# KEY_SCHEMATIC.net
KiCad netlist of a schematic drawn in EasyEDA
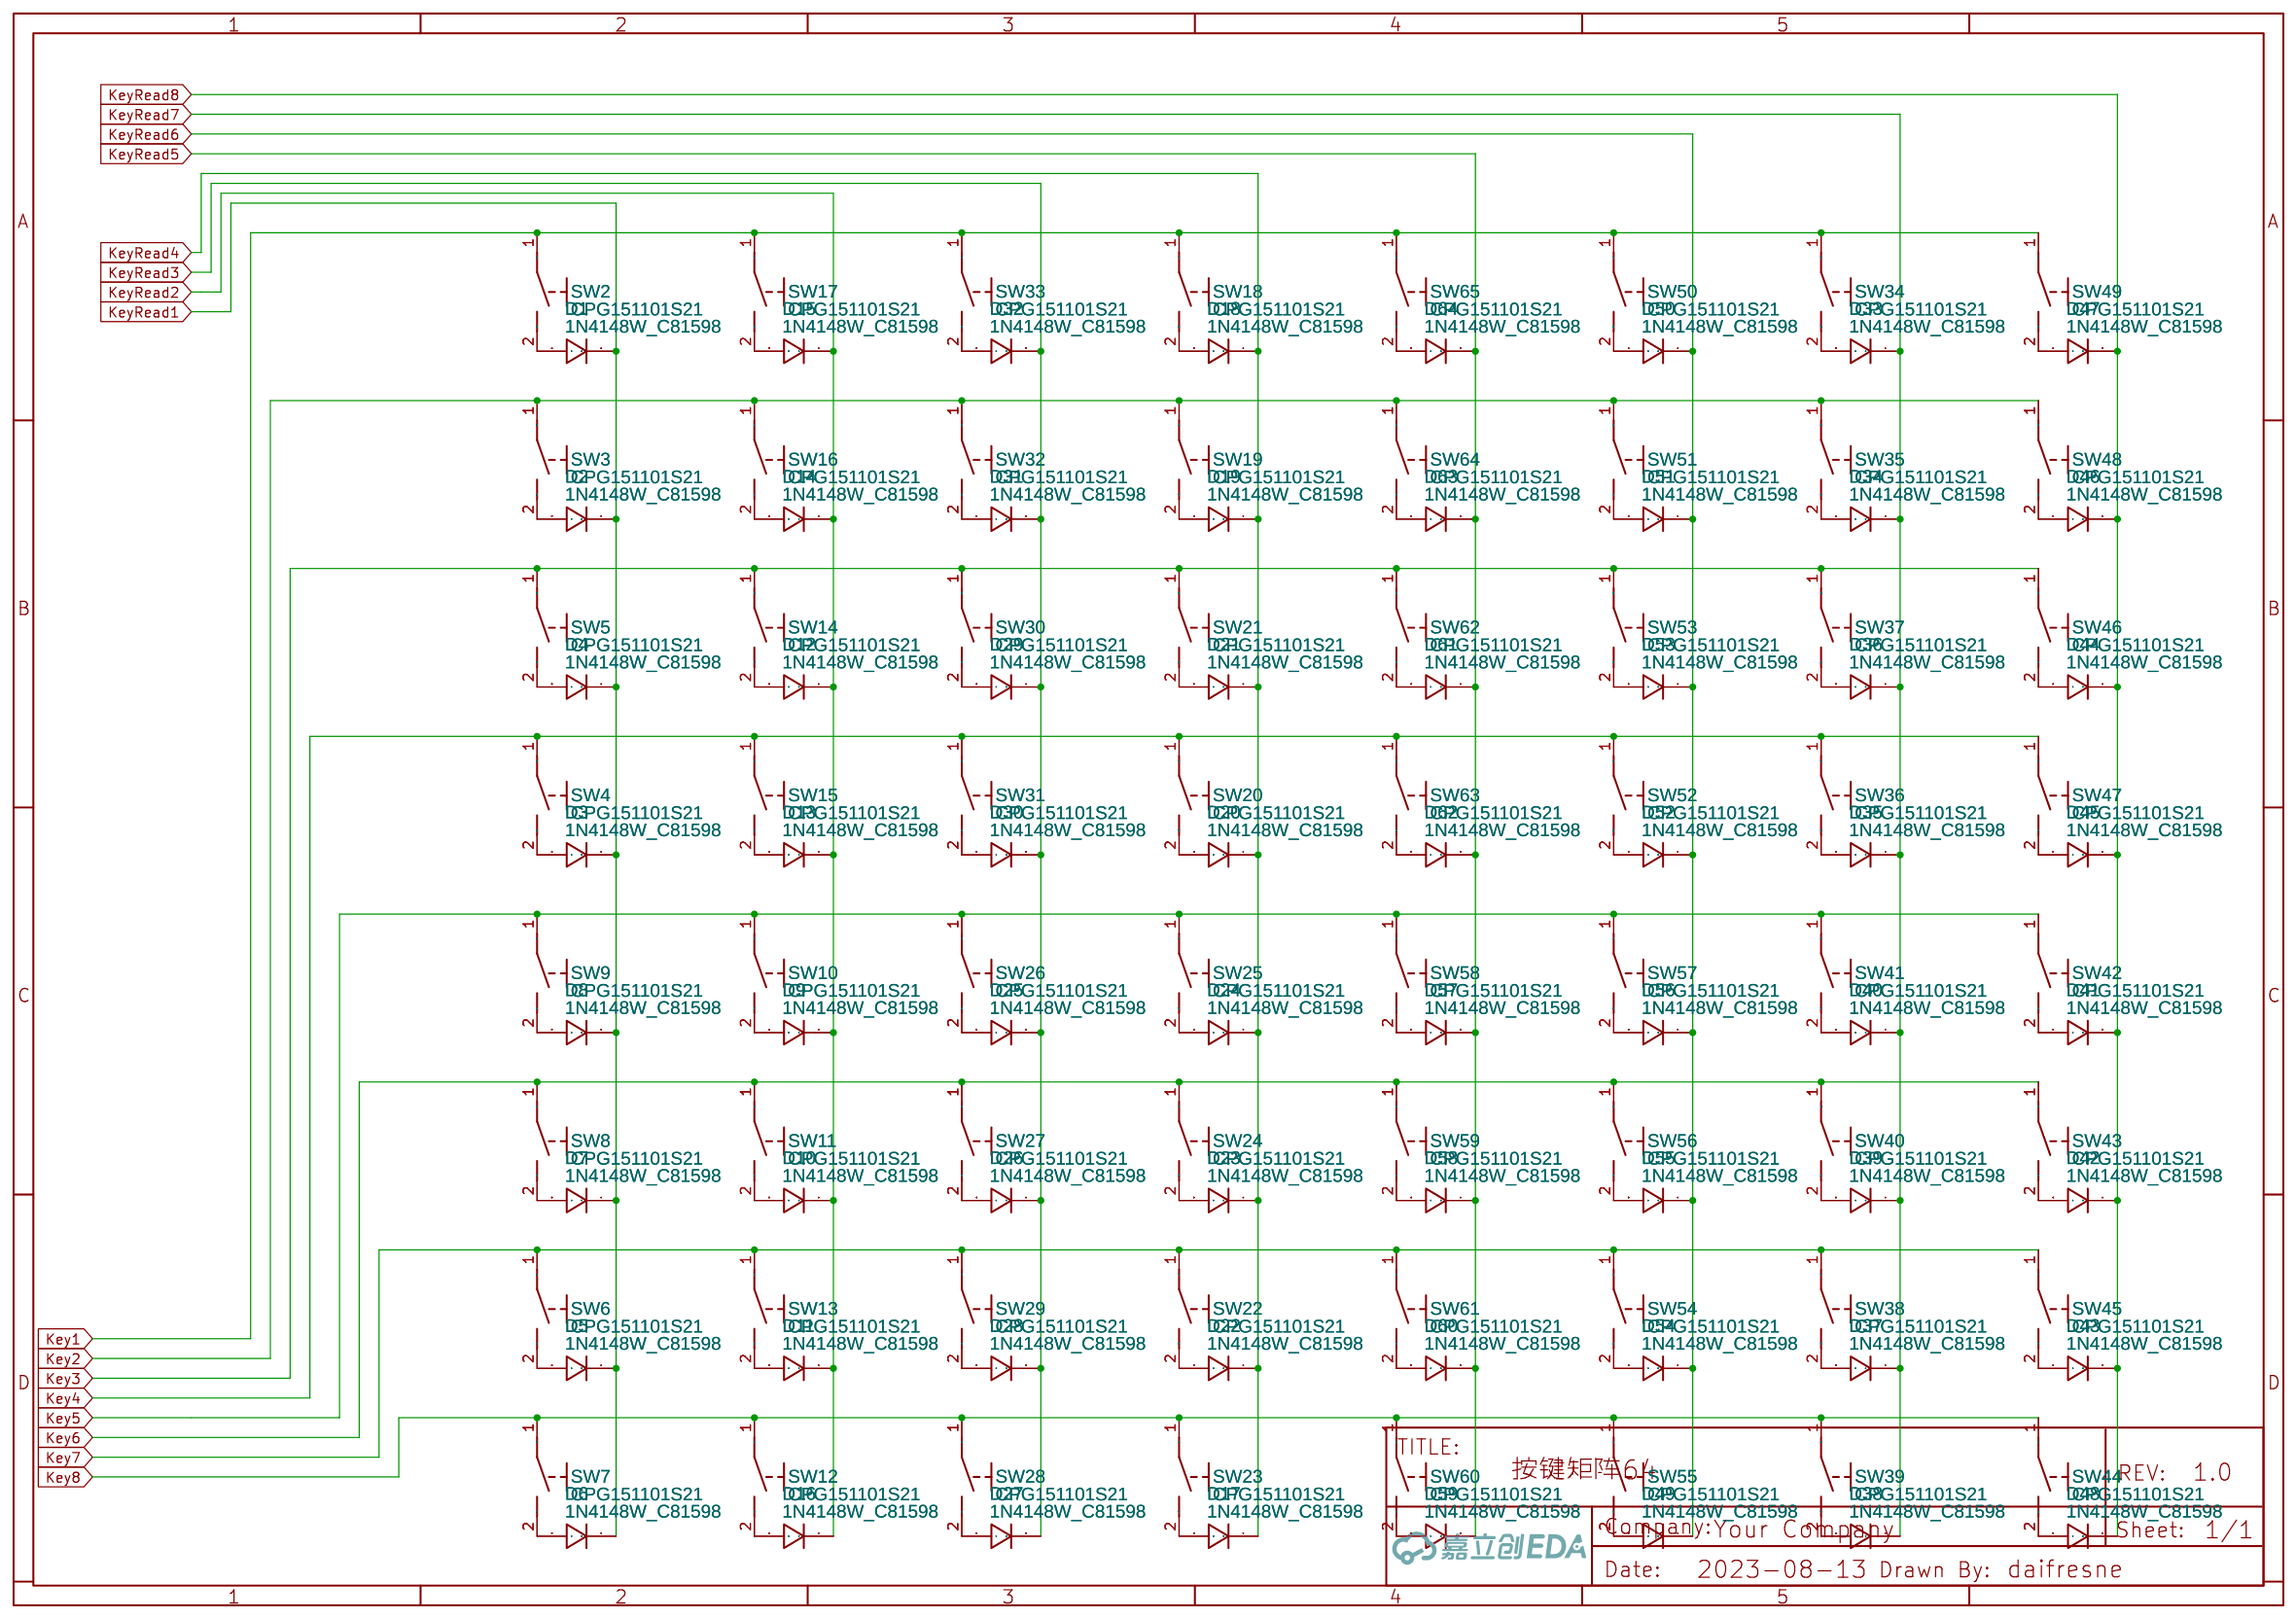
[diagram p0: 按键矩阵64]
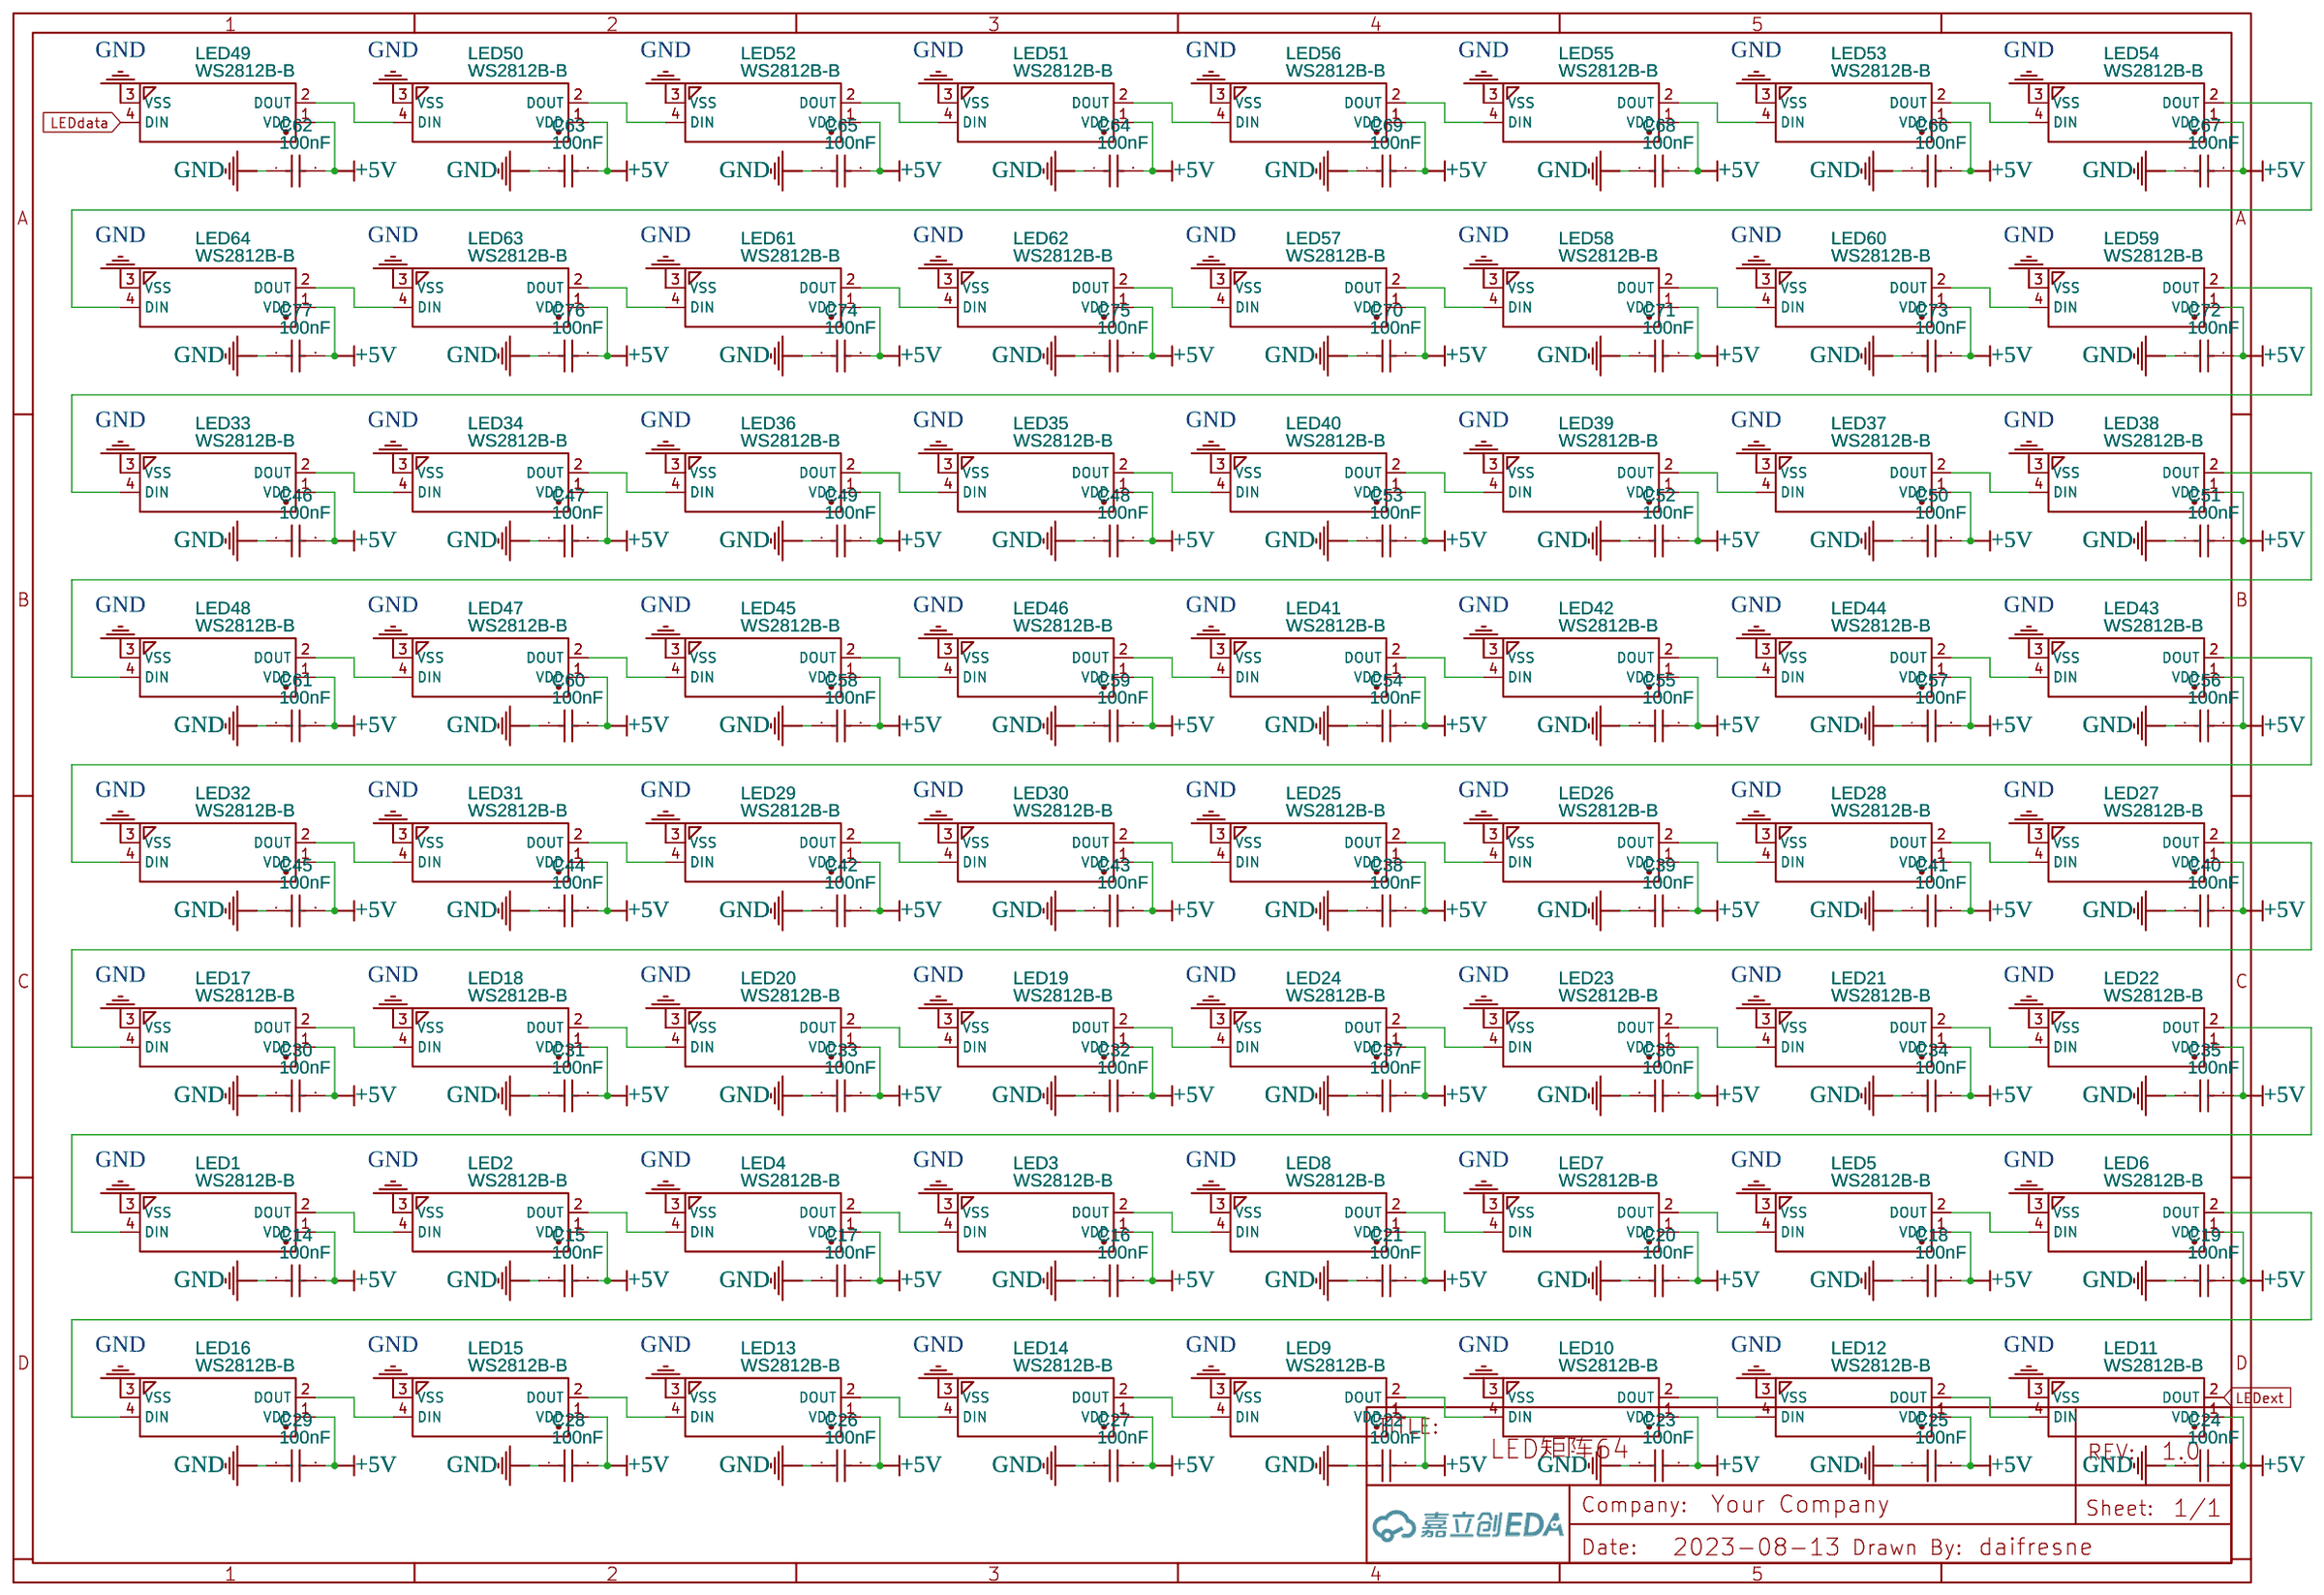
[diagram p1: LED矩阵64]

(export (version "E")
  (design (tool "Eeschema 10.0.6"))
  (components
    (comp (ref "D1")
      (value "1N4148W_C81598")
      (fields (field (name "Manufacturer") "ST(先科)"))
      (libsource (lib "") (part "1N4148W_C81598"))
    )
    (comp (ref "D2")
      (value "1N4148W_C81598")
      (fields (field (name "Manufacturer") "ST(先科)"))
      (libsource (lib "") (part "1N4148W_C81598"))
    )
    (comp (ref "D3")
      (value "1N4148W_C81598")
      (fields (field (name "Manufacturer") "ST(先科)"))
      (libsource (lib "") (part "1N4148W_C81598"))
    )
    (comp (ref "D4")
      (value "1N4148W_C81598")
      (fields (field (name "Manufacturer") "ST(先科)"))
      (libsource (lib "") (part "1N4148W_C81598"))
    )
    (comp (ref "D5")
      (value "1N4148W_C81598")
      (fields (field (name "Manufacturer") "ST(先科)"))
      (libsource (lib "") (part "1N4148W_C81598"))
    )
    (comp (ref "D6")
      (value "1N4148W_C81598")
      (fields (field (name "Manufacturer") "ST(先科)"))
      (libsource (lib "") (part "1N4148W_C81598"))
    )
    (comp (ref "D7")
      (value "1N4148W_C81598")
      (fields (field (name "Manufacturer") "ST(先科)"))
      (libsource (lib "") (part "1N4148W_C81598"))
    )
    (comp (ref "D8")
      (value "1N4148W_C81598")
      (fields (field (name "Manufacturer") "ST(先科)"))
      (libsource (lib "") (part "1N4148W_C81598"))
    )
    (comp (ref "D9")
      (value "1N4148W_C81598")
      (fields (field (name "Manufacturer") "ST(先科)"))
      (libsource (lib "") (part "1N4148W_C81598"))
    )
    (comp (ref "D10")
      (value "1N4148W_C81598")
      (fields (field (name "Manufacturer") "ST(先科)"))
      (libsource (lib "") (part "1N4148W_C81598"))
    )
    (comp (ref "D11")
      (value "1N4148W_C81598")
      (fields (field (name "Manufacturer") "ST(先科)"))
      (libsource (lib "") (part "1N4148W_C81598"))
    )
    (comp (ref "D12")
      (value "1N4148W_C81598")
      (fields (field (name "Manufacturer") "ST(先科)"))
      (libsource (lib "") (part "1N4148W_C81598"))
    )
    (comp (ref "D13")
      (value "1N4148W_C81598")
      (fields (field (name "Manufacturer") "ST(先科)"))
      (libsource (lib "") (part "1N4148W_C81598"))
    )
    (comp (ref "D14")
      (value "1N4148W_C81598")
      (fields (field (name "Manufacturer") "ST(先科)"))
      (libsource (lib "") (part "1N4148W_C81598"))
    )
    (comp (ref "D15")
      (value "1N4148W_C81598")
      (fields (field (name "Manufacturer") "ST(先科)"))
      (libsource (lib "") (part "1N4148W_C81598"))
    )
    (comp (ref "D16")
      (value "1N4148W_C81598")
      (fields (field (name "Manufacturer") "ST(先科)"))
      (libsource (lib "") (part "1N4148W_C81598"))
    )
    (comp (ref "D17")
      (value "1N4148W_C81598")
      (fields (field (name "Manufacturer") "ST(先科)"))
      (libsource (lib "") (part "1N4148W_C81598"))
    )
    (comp (ref "D18")
      (value "1N4148W_C81598")
      (fields (field (name "Manufacturer") "ST(先科)"))
      (libsource (lib "") (part "1N4148W_C81598"))
    )
    (comp (ref "D19")
      (value "1N4148W_C81598")
      (fields (field (name "Manufacturer") "ST(先科)"))
      (libsource (lib "") (part "1N4148W_C81598"))
    )
    (comp (ref "D20")
      (value "1N4148W_C81598")
      (fields (field (name "Manufacturer") "ST(先科)"))
      (libsource (lib "") (part "1N4148W_C81598"))
    )
    (comp (ref "D21")
      (value "1N4148W_C81598")
      (fields (field (name "Manufacturer") "ST(先科)"))
      (libsource (lib "") (part "1N4148W_C81598"))
    )
    (comp (ref "D22")
      (value "1N4148W_C81598")
      (fields (field (name "Manufacturer") "ST(先科)"))
      (libsource (lib "") (part "1N4148W_C81598"))
    )
    (comp (ref "D23")
      (value "1N4148W_C81598")
      (fields (field (name "Manufacturer") "ST(先科)"))
      (libsource (lib "") (part "1N4148W_C81598"))
    )
    (comp (ref "D24")
      (value "1N4148W_C81598")
      (fields (field (name "Manufacturer") "ST(先科)"))
      (libsource (lib "") (part "1N4148W_C81598"))
    )
    (comp (ref "D25")
      (value "1N4148W_C81598")
      (fields (field (name "Manufacturer") "ST(先科)"))
      (libsource (lib "") (part "1N4148W_C81598"))
    )
    (comp (ref "D26")
      (value "1N4148W_C81598")
      (fields (field (name "Manufacturer") "ST(先科)"))
      (libsource (lib "") (part "1N4148W_C81598"))
    )
    (comp (ref "D27")
      (value "1N4148W_C81598")
      (fields (field (name "Manufacturer") "ST(先科)"))
      (libsource (lib "") (part "1N4148W_C81598"))
    )
    (comp (ref "D28")
      (value "1N4148W_C81598")
      (fields (field (name "Manufacturer") "ST(先科)"))
      (libsource (lib "") (part "1N4148W_C81598"))
    )
    (comp (ref "D29")
      (value "1N4148W_C81598")
      (fields (field (name "Manufacturer") "ST(先科)"))
      (libsource (lib "") (part "1N4148W_C81598"))
    )
    (comp (ref "D30")
      (value "1N4148W_C81598")
      (fields (field (name "Manufacturer") "ST(先科)"))
      (libsource (lib "") (part "1N4148W_C81598"))
    )
    (comp (ref "D31")
      (value "1N4148W_C81598")
      (fields (field (name "Manufacturer") "ST(先科)"))
      (libsource (lib "") (part "1N4148W_C81598"))
    )
    (comp (ref "D32")
      (value "1N4148W_C81598")
      (fields (field (name "Manufacturer") "ST(先科)"))
      (libsource (lib "") (part "1N4148W_C81598"))
    )
    (comp (ref "D33")
      (value "1N4148W_C81598")
      (fields (field (name "Manufacturer") "ST(先科)"))
      (libsource (lib "") (part "1N4148W_C81598"))
    )
    (comp (ref "D34")
      (value "1N4148W_C81598")
      (fields (field (name "Manufacturer") "ST(先科)"))
      (libsource (lib "") (part "1N4148W_C81598"))
    )
    (comp (ref "D35")
      (value "1N4148W_C81598")
      (fields (field (name "Manufacturer") "ST(先科)"))
      (libsource (lib "") (part "1N4148W_C81598"))
    )
    (comp (ref "D36")
      (value "1N4148W_C81598")
      (fields (field (name "Manufacturer") "ST(先科)"))
      (libsource (lib "") (part "1N4148W_C81598"))
    )
    (comp (ref "D37")
      (value "1N4148W_C81598")
      (fields (field (name "Manufacturer") "ST(先科)"))
      (libsource (lib "") (part "1N4148W_C81598"))
    )
    (comp (ref "D38")
      (value "1N4148W_C81598")
      (fields (field (name "Manufacturer") "ST(先科)"))
      (libsource (lib "") (part "1N4148W_C81598"))
    )
    (comp (ref "D39")
      (value "1N4148W_C81598")
      (fields (field (name "Manufacturer") "ST(先科)"))
      (libsource (lib "") (part "1N4148W_C81598"))
    )
    (comp (ref "D40")
      (value "1N4148W_C81598")
      (fields (field (name "Manufacturer") "ST(先科)"))
      (libsource (lib "") (part "1N4148W_C81598"))
    )
    (comp (ref "D41")
      (value "1N4148W_C81598")
      (fields (field (name "Manufacturer") "ST(先科)"))
      (libsource (lib "") (part "1N4148W_C81598"))
    )
    (comp (ref "D42")
      (value "1N4148W_C81598")
      (fields (field (name "Manufacturer") "ST(先科)"))
      (libsource (lib "") (part "1N4148W_C81598"))
    )
    (comp (ref "D43")
      (value "1N4148W_C81598")
      (fields (field (name "Manufacturer") "ST(先科)"))
      (libsource (lib "") (part "1N4148W_C81598"))
    )
    (comp (ref "D44")
      (value "1N4148W_C81598")
      (fields (field (name "Manufacturer") "ST(先科)"))
      (libsource (lib "") (part "1N4148W_C81598"))
    )
    (comp (ref "D45")
      (value "1N4148W_C81598")
      (fields (field (name "Manufacturer") "ST(先科)"))
      (libsource (lib "") (part "1N4148W_C81598"))
    )
    (comp (ref "D46")
      (value "1N4148W_C81598")
      (fields (field (name "Manufacturer") "ST(先科)"))
      (libsource (lib "") (part "1N4148W_C81598"))
    )
    (comp (ref "D47")
      (value "1N4148W_C81598")
      (fields (field (name "Manufacturer") "ST(先科)"))
      (libsource (lib "") (part "1N4148W_C81598"))
    )
    (comp (ref "D48")
      (value "1N4148W_C81598")
      (fields (field (name "Manufacturer") "ST(先科)"))
      (libsource (lib "") (part "1N4148W_C81598"))
    )
    (comp (ref "D49")
      (value "1N4148W_C81598")
      (fields (field (name "Manufacturer") "ST(先科)"))
      (libsource (lib "") (part "1N4148W_C81598"))
    )
    (comp (ref "D50")
      (value "1N4148W_C81598")
      (fields (field (name "Manufacturer") "ST(先科)"))
      (libsource (lib "") (part "1N4148W_C81598"))
    )
    (comp (ref "D51")
      (value "1N4148W_C81598")
      (fields (field (name "Manufacturer") "ST(先科)"))
      (libsource (lib "") (part "1N4148W_C81598"))
    )
    (comp (ref "D52")
      (value "1N4148W_C81598")
      (fields (field (name "Manufacturer") "ST(先科)"))
      (libsource (lib "") (part "1N4148W_C81598"))
    )
    (comp (ref "D53")
      (value "1N4148W_C81598")
      (fields (field (name "Manufacturer") "ST(先科)"))
      (libsource (lib "") (part "1N4148W_C81598"))
    )
    (comp (ref "D54")
      (value "1N4148W_C81598")
      (fields (field (name "Manufacturer") "ST(先科)"))
      (libsource (lib "") (part "1N4148W_C81598"))
    )
    (comp (ref "D55")
      (value "1N4148W_C81598")
      (fields (field (name "Manufacturer") "ST(先科)"))
      (libsource (lib "") (part "1N4148W_C81598"))
    )
    (comp (ref "D56")
      (value "1N4148W_C81598")
      (fields (field (name "Manufacturer") "ST(先科)"))
      (libsource (lib "") (part "1N4148W_C81598"))
    )
    (comp (ref "D57")
      (value "1N4148W_C81598")
      (fields (field (name "Manufacturer") "ST(先科)"))
      (libsource (lib "") (part "1N4148W_C81598"))
    )
    (comp (ref "D58")
      (value "1N4148W_C81598")
      (fields (field (name "Manufacturer") "ST(先科)"))
      (libsource (lib "") (part "1N4148W_C81598"))
    )
    (comp (ref "D59")
      (value "1N4148W_C81598")
      (fields (field (name "Manufacturer") "ST(先科)"))
      (libsource (lib "") (part "1N4148W_C81598"))
    )
    (comp (ref "D60")
      (value "1N4148W_C81598")
      (fields (field (name "Manufacturer") "ST(先科)"))
      (libsource (lib "") (part "1N4148W_C81598"))
    )
    (comp (ref "D61")
      (value "1N4148W_C81598")
      (fields (field (name "Manufacturer") "ST(先科)"))
      (libsource (lib "") (part "1N4148W_C81598"))
    )
    (comp (ref "D62")
      (value "1N4148W_C81598")
      (fields (field (name "Manufacturer") "ST(先科)"))
      (libsource (lib "") (part "1N4148W_C81598"))
    )
    (comp (ref "D63")
      (value "1N4148W_C81598")
      (fields (field (name "Manufacturer") "ST(先科)"))
      (libsource (lib "") (part "1N4148W_C81598"))
    )
    (comp (ref "D64")
      (value "1N4148W_C81598")
      (fields (field (name "Manufacturer") "ST(先科)"))
      (libsource (lib "") (part "1N4148W_C81598"))
    )
    (comp (ref "SW2")
      (value "CPG151101S21")
      (fields (field (name "Manufacturer") "Kailh(凯华)"))
      (libsource (lib "") (part "CPG151101S21"))
    )
    (comp (ref "SW3")
      (value "CPG151101S21")
      (fields (field (name "Manufacturer") "Kailh(凯华)"))
      (libsource (lib "") (part "CPG151101S21"))
    )
    (comp (ref "SW4")
      (value "CPG151101S21")
      (fields (field (name "Manufacturer") "Kailh(凯华)"))
      (libsource (lib "") (part "CPG151101S21"))
    )
    (comp (ref "SW5")
      (value "CPG151101S21")
      (fields (field (name "Manufacturer") "Kailh(凯华)"))
      (libsource (lib "") (part "CPG151101S21"))
    )
    (comp (ref "SW6")
      (value "CPG151101S21")
      (fields (field (name "Manufacturer") "Kailh(凯华)"))
      (libsource (lib "") (part "CPG151101S21"))
    )
    (comp (ref "SW7")
      (value "CPG151101S21")
      (fields (field (name "Manufacturer") "Kailh(凯华)"))
      (libsource (lib "") (part "CPG151101S21"))
    )
    (comp (ref "SW8")
      (value "CPG151101S21")
      (fields (field (name "Manufacturer") "Kailh(凯华)"))
      (libsource (lib "") (part "CPG151101S21"))
    )
    (comp (ref "SW9")
      (value "CPG151101S21")
      (fields (field (name "Manufacturer") "Kailh(凯华)"))
      (libsource (lib "") (part "CPG151101S21"))
    )
    (comp (ref "SW10")
      (value "CPG151101S21")
      (fields (field (name "Manufacturer") "Kailh(凯华)"))
      (libsource (lib "") (part "CPG151101S21"))
    )
    (comp (ref "SW11")
      (value "CPG151101S21")
      (fields (field (name "Manufacturer") "Kailh(凯华)"))
      (libsource (lib "") (part "CPG151101S21"))
    )
    (comp (ref "SW12")
      (value "CPG151101S21")
      (fields (field (name "Manufacturer") "Kailh(凯华)"))
      (libsource (lib "") (part "CPG151101S21"))
    )
    (comp (ref "SW13")
      (value "CPG151101S21")
      (fields (field (name "Manufacturer") "Kailh(凯华)"))
      (libsource (lib "") (part "CPG151101S21"))
    )
    (comp (ref "SW14")
      (value "CPG151101S21")
      (fields (field (name "Manufacturer") "Kailh(凯华)"))
      (libsource (lib "") (part "CPG151101S21"))
    )
    (comp (ref "SW15")
      (value "CPG151101S21")
      (fields (field (name "Manufacturer") "Kailh(凯华)"))
      (libsource (lib "") (part "CPG151101S21"))
    )
    (comp (ref "SW16")
      (value "CPG151101S21")
      (fields (field (name "Manufacturer") "Kailh(凯华)"))
      (libsource (lib "") (part "CPG151101S21"))
    )
    (comp (ref "SW17")
      (value "CPG151101S21")
      (fields (field (name "Manufacturer") "Kailh(凯华)"))
      (libsource (lib "") (part "CPG151101S21"))
    )
    (comp (ref "SW18")
      (value "CPG151101S21")
      (fields (field (name "Manufacturer") "Kailh(凯华)"))
      (libsource (lib "") (part "CPG151101S21"))
    )
    (comp (ref "SW19")
      (value "CPG151101S21")
      (fields (field (name "Manufacturer") "Kailh(凯华)"))
      (libsource (lib "") (part "CPG151101S21"))
    )
    (comp (ref "SW20")
      (value "CPG151101S21")
      (fields (field (name "Manufacturer") "Kailh(凯华)"))
      (libsource (lib "") (part "CPG151101S21"))
    )
    (comp (ref "SW21")
      (value "CPG151101S21")
      (fields (field (name "Manufacturer") "Kailh(凯华)"))
      (libsource (lib "") (part "CPG151101S21"))
    )
    (comp (ref "SW22")
      (value "CPG151101S21")
      (fields (field (name "Manufacturer") "Kailh(凯华)"))
      (libsource (lib "") (part "CPG151101S21"))
    )
    (comp (ref "SW23")
      (value "CPG151101S21")
      (fields (field (name "Manufacturer") "Kailh(凯华)"))
      (libsource (lib "") (part "CPG151101S21"))
    )
    (comp (ref "SW24")
      (value "CPG151101S21")
      (fields (field (name "Manufacturer") "Kailh(凯华)"))
      (libsource (lib "") (part "CPG151101S21"))
    )
    (comp (ref "SW25")
      (value "CPG151101S21")
      (fields (field (name "Manufacturer") "Kailh(凯华)"))
      (libsource (lib "") (part "CPG151101S21"))
    )
    (comp (ref "SW26")
      (value "CPG151101S21")
      (fields (field (name "Manufacturer") "Kailh(凯华)"))
      (libsource (lib "") (part "CPG151101S21"))
    )
    (comp (ref "SW27")
      (value "CPG151101S21")
      (fields (field (name "Manufacturer") "Kailh(凯华)"))
      (libsource (lib "") (part "CPG151101S21"))
    )
    (comp (ref "SW28")
      (value "CPG151101S21")
      (fields (field (name "Manufacturer") "Kailh(凯华)"))
      (libsource (lib "") (part "CPG151101S21"))
    )
    (comp (ref "SW29")
      (value "CPG151101S21")
      (fields (field (name "Manufacturer") "Kailh(凯华)"))
      (libsource (lib "") (part "CPG151101S21"))
    )
    (comp (ref "SW30")
      (value "CPG151101S21")
      (fields (field (name "Manufacturer") "Kailh(凯华)"))
      (libsource (lib "") (part "CPG151101S21"))
    )
    (comp (ref "SW31")
      (value "CPG151101S21")
      (fields (field (name "Manufacturer") "Kailh(凯华)"))
      (libsource (lib "") (part "CPG151101S21"))
    )
    (comp (ref "SW32")
      (value "CPG151101S21")
      (fields (field (name "Manufacturer") "Kailh(凯华)"))
      (libsource (lib "") (part "CPG151101S21"))
    )
    (comp (ref "SW33")
      (value "CPG151101S21")
      (fields (field (name "Manufacturer") "Kailh(凯华)"))
      (libsource (lib "") (part "CPG151101S21"))
    )
    (comp (ref "SW34")
      (value "CPG151101S21")
      (fields (field (name "Manufacturer") "Kailh(凯华)"))
      (libsource (lib "") (part "CPG151101S21"))
    )
    (comp (ref "SW35")
      (value "CPG151101S21")
      (fields (field (name "Manufacturer") "Kailh(凯华)"))
      (libsource (lib "") (part "CPG151101S21"))
    )
    (comp (ref "SW36")
      (value "CPG151101S21")
      (fields (field (name "Manufacturer") "Kailh(凯华)"))
      (libsource (lib "") (part "CPG151101S21"))
    )
    (comp (ref "SW37")
      (value "CPG151101S21")
      (fields (field (name "Manufacturer") "Kailh(凯华)"))
      (libsource (lib "") (part "CPG151101S21"))
    )
    (comp (ref "SW38")
      (value "CPG151101S21")
      (fields (field (name "Manufacturer") "Kailh(凯华)"))
      (libsource (lib "") (part "CPG151101S21"))
    )
    (comp (ref "SW39")
      (value "CPG151101S21")
      (fields (field (name "Manufacturer") "Kailh(凯华)"))
      (libsource (lib "") (part "CPG151101S21"))
    )
    (comp (ref "SW40")
      (value "CPG151101S21")
      (fields (field (name "Manufacturer") "Kailh(凯华)"))
      (libsource (lib "") (part "CPG151101S21"))
    )
    (comp (ref "SW41")
      (value "CPG151101S21")
      (fields (field (name "Manufacturer") "Kailh(凯华)"))
      (libsource (lib "") (part "CPG151101S21"))
    )
    (comp (ref "SW42")
      (value "CPG151101S21")
      (fields (field (name "Manufacturer") "Kailh(凯华)"))
      (libsource (lib "") (part "CPG151101S21"))
    )
    (comp (ref "SW43")
      (value "CPG151101S21")
      (fields (field (name "Manufacturer") "Kailh(凯华)"))
      (libsource (lib "") (part "CPG151101S21"))
    )
    (comp (ref "SW44")
      (value "CPG151101S21")
      (fields (field (name "Manufacturer") "Kailh(凯华)"))
      (libsource (lib "") (part "CPG151101S21"))
    )
    (comp (ref "SW45")
      (value "CPG151101S21")
      (fields (field (name "Manufacturer") "Kailh(凯华)"))
      (libsource (lib "") (part "CPG151101S21"))
    )
    (comp (ref "SW46")
      (value "CPG151101S21")
      (fields (field (name "Manufacturer") "Kailh(凯华)"))
      (libsource (lib "") (part "CPG151101S21"))
    )
    (comp (ref "SW47")
      (value "CPG151101S21")
      (fields (field (name "Manufacturer") "Kailh(凯华)"))
      (libsource (lib "") (part "CPG151101S21"))
    )
    (comp (ref "SW48")
      (value "CPG151101S21")
      (fields (field (name "Manufacturer") "Kailh(凯华)"))
      (libsource (lib "") (part "CPG151101S21"))
    )
    (comp (ref "SW49")
      (value "CPG151101S21")
      (fields (field (name "Manufacturer") "Kailh(凯华)"))
      (libsource (lib "") (part "CPG151101S21"))
    )
    (comp (ref "SW50")
      (value "CPG151101S21")
      (fields (field (name "Manufacturer") "Kailh(凯华)"))
      (libsource (lib "") (part "CPG151101S21"))
    )
    (comp (ref "SW51")
      (value "CPG151101S21")
      (fields (field (name "Manufacturer") "Kailh(凯华)"))
      (libsource (lib "") (part "CPG151101S21"))
    )
    (comp (ref "SW52")
      (value "CPG151101S21")
      (fields (field (name "Manufacturer") "Kailh(凯华)"))
      (libsource (lib "") (part "CPG151101S21"))
    )
    (comp (ref "SW53")
      (value "CPG151101S21")
      (fields (field (name "Manufacturer") "Kailh(凯华)"))
      (libsource (lib "") (part "CPG151101S21"))
    )
    (comp (ref "SW54")
      (value "CPG151101S21")
      (fields (field (name "Manufacturer") "Kailh(凯华)"))
      (libsource (lib "") (part "CPG151101S21"))
    )
    (comp (ref "SW55")
      (value "CPG151101S21")
      (fields (field (name "Manufacturer") "Kailh(凯华)"))
      (libsource (lib "") (part "CPG151101S21"))
    )
    (comp (ref "SW56")
      (value "CPG151101S21")
      (fields (field (name "Manufacturer") "Kailh(凯华)"))
      (libsource (lib "") (part "CPG151101S21"))
    )
    (comp (ref "SW57")
      (value "CPG151101S21")
      (fields (field (name "Manufacturer") "Kailh(凯华)"))
      (libsource (lib "") (part "CPG151101S21"))
    )
    (comp (ref "SW58")
      (value "CPG151101S21")
      (fields (field (name "Manufacturer") "Kailh(凯华)"))
      (libsource (lib "") (part "CPG151101S21"))
    )
    (comp (ref "SW59")
      (value "CPG151101S21")
      (fields (field (name "Manufacturer") "Kailh(凯华)"))
      (libsource (lib "") (part "CPG151101S21"))
    )
    (comp (ref "SW60")
      (value "CPG151101S21")
      (fields (field (name "Manufacturer") "Kailh(凯华)"))
      (libsource (lib "") (part "CPG151101S21"))
    )
    (comp (ref "SW61")
      (value "CPG151101S21")
      (fields (field (name "Manufacturer") "Kailh(凯华)"))
      (libsource (lib "") (part "CPG151101S21"))
    )
    (comp (ref "SW62")
      (value "CPG151101S21")
      (fields (field (name "Manufacturer") "Kailh(凯华)"))
      (libsource (lib "") (part "CPG151101S21"))
    )
    (comp (ref "SW63")
      (value "CPG151101S21")
      (fields (field (name "Manufacturer") "Kailh(凯华)"))
      (libsource (lib "") (part "CPG151101S21"))
    )
    (comp (ref "SW64")
      (value "CPG151101S21")
      (fields (field (name "Manufacturer") "Kailh(凯华)"))
      (libsource (lib "") (part "CPG151101S21"))
    )
    (comp (ref "SW65")
      (value "CPG151101S21")
      (fields (field (name "Manufacturer") "Kailh(凯华)"))
      (libsource (lib "") (part "CPG151101S21"))
    )
    (comp (ref "C14")
      (value "100nF")
      (fields
        (field (name "Manufacturer Part") "CC0603KRX7R8BB104")
        (field (name "Manufacturer") "YAGEO(国巨)")
      )
      (libsource (lib "") (part "CC0603KRX7R8BB104"))
    )
    (comp (ref "C15")
      (value "100nF")
      (fields
        (field (name "Manufacturer Part") "CC0603KRX7R8BB104")
        (field (name "Manufacturer") "YAGEO(国巨)")
      )
      (libsource (lib "") (part "CC0603KRX7R8BB104"))
    )
    (comp (ref "C16")
      (value "100nF")
      (fields
        (field (name "Manufacturer Part") "CC0603KRX7R8BB104")
        (field (name "Manufacturer") "YAGEO(国巨)")
      )
      (libsource (lib "") (part "CC0603KRX7R8BB104"))
    )
    (comp (ref "C17")
      (value "100nF")
      (fields
        (field (name "Manufacturer Part") "CC0603KRX7R8BB104")
        (field (name "Manufacturer") "YAGEO(国巨)")
      )
      (libsource (lib "") (part "CC0603KRX7R8BB104"))
    )
    (comp (ref "C18")
      (value "100nF")
      (fields
        (field (name "Manufacturer Part") "CC0603KRX7R8BB104")
        (field (name "Manufacturer") "YAGEO(国巨)")
      )
      (libsource (lib "") (part "CC0603KRX7R8BB104"))
    )
    (comp (ref "C19")
      (value "100nF")
      (fields
        (field (name "Manufacturer Part") "CC0603KRX7R8BB104")
        (field (name "Manufacturer") "YAGEO(国巨)")
      )
      (libsource (lib "") (part "CC0603KRX7R8BB104"))
    )
    (comp (ref "C20")
      (value "100nF")
      (fields
        (field (name "Manufacturer Part") "CC0603KRX7R8BB104")
        (field (name "Manufacturer") "YAGEO(国巨)")
      )
      (libsource (lib "") (part "CC0603KRX7R8BB104"))
    )
    (comp (ref "C21")
      (value "100nF")
      (fields
        (field (name "Manufacturer Part") "CC0603KRX7R8BB104")
        (field (name "Manufacturer") "YAGEO(国巨)")
      )
      (libsource (lib "") (part "CC0603KRX7R8BB104"))
    )
    (comp (ref "C22")
      (value "100nF")
      (fields
        (field (name "Manufacturer Part") "CC0603KRX7R8BB104")
        (field (name "Manufacturer") "YAGEO(国巨)")
      )
      (libsource (lib "") (part "CC0603KRX7R8BB104"))
    )
    (comp (ref "C23")
      (value "100nF")
      (fields
        (field (name "Manufacturer Part") "CC0603KRX7R8BB104")
        (field (name "Manufacturer") "YAGEO(国巨)")
      )
      (libsource (lib "") (part "CC0603KRX7R8BB104"))
    )
    (comp (ref "C24")
      (value "100nF")
      (fields
        (field (name "Manufacturer Part") "CC0603KRX7R8BB104")
        (field (name "Manufacturer") "YAGEO(国巨)")
      )
      (libsource (lib "") (part "CC0603KRX7R8BB104"))
    )
    (comp (ref "C25")
      (value "100nF")
      (fields
        (field (name "Manufacturer Part") "CC0603KRX7R8BB104")
        (field (name "Manufacturer") "YAGEO(国巨)")
      )
      (libsource (lib "") (part "CC0603KRX7R8BB104"))
    )
    (comp (ref "C26")
      (value "100nF")
      (fields
        (field (name "Manufacturer Part") "CC0603KRX7R8BB104")
        (field (name "Manufacturer") "YAGEO(国巨)")
      )
      (libsource (lib "") (part "CC0603KRX7R8BB104"))
    )
    (comp (ref "C27")
      (value "100nF")
      (fields
        (field (name "Manufacturer Part") "CC0603KRX7R8BB104")
        (field (name "Manufacturer") "YAGEO(国巨)")
      )
      (libsource (lib "") (part "CC0603KRX7R8BB104"))
    )
    (comp (ref "C28")
      (value "100nF")
      (fields
        (field (name "Manufacturer Part") "CC0603KRX7R8BB104")
        (field (name "Manufacturer") "YAGEO(国巨)")
      )
      (libsource (lib "") (part "CC0603KRX7R8BB104"))
    )
    (comp (ref "C29")
      (value "100nF")
      (fields
        (field (name "Manufacturer Part") "CC0603KRX7R8BB104")
        (field (name "Manufacturer") "YAGEO(国巨)")
      )
      (libsource (lib "") (part "CC0603KRX7R8BB104"))
    )
    (comp (ref "C30")
      (value "100nF")
      (fields
        (field (name "Manufacturer Part") "CC0603KRX7R8BB104")
        (field (name "Manufacturer") "YAGEO(国巨)")
      )
      (libsource (lib "") (part "CC0603KRX7R8BB104"))
    )
    (comp (ref "C31")
      (value "100nF")
      (fields
        (field (name "Manufacturer Part") "CC0603KRX7R8BB104")
        (field (name "Manufacturer") "YAGEO(国巨)")
      )
      (libsource (lib "") (part "CC0603KRX7R8BB104"))
    )
    (comp (ref "C32")
      (value "100nF")
      (fields
        (field (name "Manufacturer Part") "CC0603KRX7R8BB104")
        (field (name "Manufacturer") "YAGEO(国巨)")
      )
      (libsource (lib "") (part "CC0603KRX7R8BB104"))
    )
    (comp (ref "C33")
      (value "100nF")
      (fields
        (field (name "Manufacturer Part") "CC0603KRX7R8BB104")
        (field (name "Manufacturer") "YAGEO(国巨)")
      )
      (libsource (lib "") (part "CC0603KRX7R8BB104"))
    )
    (comp (ref "C34")
      (value "100nF")
      (fields
        (field (name "Manufacturer Part") "CC0603KRX7R8BB104")
        (field (name "Manufacturer") "YAGEO(国巨)")
      )
      (libsource (lib "") (part "CC0603KRX7R8BB104"))
    )
    (comp (ref "C35")
      (value "100nF")
      (fields
        (field (name "Manufacturer Part") "CC0603KRX7R8BB104")
        (field (name "Manufacturer") "YAGEO(国巨)")
      )
      (libsource (lib "") (part "CC0603KRX7R8BB104"))
    )
    (comp (ref "C36")
      (value "100nF")
      (fields
        (field (name "Manufacturer Part") "CC0603KRX7R8BB104")
        (field (name "Manufacturer") "YAGEO(国巨)")
      )
      (libsource (lib "") (part "CC0603KRX7R8BB104"))
    )
    (comp (ref "C37")
      (value "100nF")
      (fields
        (field (name "Manufacturer Part") "CC0603KRX7R8BB104")
        (field (name "Manufacturer") "YAGEO(国巨)")
      )
      (libsource (lib "") (part "CC0603KRX7R8BB104"))
    )
    (comp (ref "C38")
      (value "100nF")
      (fields
        (field (name "Manufacturer Part") "CC0603KRX7R8BB104")
        (field (name "Manufacturer") "YAGEO(国巨)")
      )
      (libsource (lib "") (part "CC0603KRX7R8BB104"))
    )
    (comp (ref "C39")
      (value "100nF")
      (fields
        (field (name "Manufacturer Part") "CC0603KRX7R8BB104")
        (field (name "Manufacturer") "YAGEO(国巨)")
      )
      (libsource (lib "") (part "CC0603KRX7R8BB104"))
    )
    (comp (ref "C40")
      (value "100nF")
      (fields
        (field (name "Manufacturer Part") "CC0603KRX7R8BB104")
        (field (name "Manufacturer") "YAGEO(国巨)")
      )
      (libsource (lib "") (part "CC0603KRX7R8BB104"))
    )
    (comp (ref "C41")
      (value "100nF")
      (fields
        (field (name "Manufacturer Part") "CC0603KRX7R8BB104")
        (field (name "Manufacturer") "YAGEO(国巨)")
      )
      (libsource (lib "") (part "CC0603KRX7R8BB104"))
    )
    (comp (ref "C42")
      (value "100nF")
      (fields
        (field (name "Manufacturer Part") "CC0603KRX7R8BB104")
        (field (name "Manufacturer") "YAGEO(国巨)")
      )
      (libsource (lib "") (part "CC0603KRX7R8BB104"))
    )
    (comp (ref "C43")
      (value "100nF")
      (fields
        (field (name "Manufacturer Part") "CC0603KRX7R8BB104")
        (field (name "Manufacturer") "YAGEO(国巨)")
      )
      (libsource (lib "") (part "CC0603KRX7R8BB104"))
    )
    (comp (ref "C44")
      (value "100nF")
      (fields
        (field (name "Manufacturer Part") "CC0603KRX7R8BB104")
        (field (name "Manufacturer") "YAGEO(国巨)")
      )
      (libsource (lib "") (part "CC0603KRX7R8BB104"))
    )
    (comp (ref "C45")
      (value "100nF")
      (fields
        (field (name "Manufacturer Part") "CC0603KRX7R8BB104")
        (field (name "Manufacturer") "YAGEO(国巨)")
      )
      (libsource (lib "") (part "CC0603KRX7R8BB104"))
    )
    (comp (ref "C46")
      (value "100nF")
      (fields
        (field (name "Manufacturer Part") "CC0603KRX7R8BB104")
        (field (name "Manufacturer") "YAGEO(国巨)")
      )
      (libsource (lib "") (part "CC0603KRX7R8BB104"))
    )
    (comp (ref "C47")
      (value "100nF")
      (fields
        (field (name "Manufacturer Part") "CC0603KRX7R8BB104")
        (field (name "Manufacturer") "YAGEO(国巨)")
      )
      (libsource (lib "") (part "CC0603KRX7R8BB104"))
    )
    (comp (ref "C48")
      (value "100nF")
      (fields
        (field (name "Manufacturer Part") "CC0603KRX7R8BB104")
        (field (name "Manufacturer") "YAGEO(国巨)")
      )
      (libsource (lib "") (part "CC0603KRX7R8BB104"))
    )
    (comp (ref "C49")
      (value "100nF")
      (fields
        (field (name "Manufacturer Part") "CC0603KRX7R8BB104")
        (field (name "Manufacturer") "YAGEO(国巨)")
      )
      (libsource (lib "") (part "CC0603KRX7R8BB104"))
    )
    (comp (ref "C50")
      (value "100nF")
      (fields
        (field (name "Manufacturer Part") "CC0603KRX7R8BB104")
        (field (name "Manufacturer") "YAGEO(国巨)")
      )
      (libsource (lib "") (part "CC0603KRX7R8BB104"))
    )
    (comp (ref "C51")
      (value "100nF")
      (fields
        (field (name "Manufacturer Part") "CC0603KRX7R8BB104")
        (field (name "Manufacturer") "YAGEO(国巨)")
      )
      (libsource (lib "") (part "CC0603KRX7R8BB104"))
    )
    (comp (ref "C52")
      (value "100nF")
      (fields
        (field (name "Manufacturer Part") "CC0603KRX7R8BB104")
        (field (name "Manufacturer") "YAGEO(国巨)")
      )
      (libsource (lib "") (part "CC0603KRX7R8BB104"))
    )
    (comp (ref "C53")
      (value "100nF")
      (fields
        (field (name "Manufacturer Part") "CC0603KRX7R8BB104")
        (field (name "Manufacturer") "YAGEO(国巨)")
      )
      (libsource (lib "") (part "CC0603KRX7R8BB104"))
    )
    (comp (ref "C54")
      (value "100nF")
      (fields
        (field (name "Manufacturer Part") "CC0603KRX7R8BB104")
        (field (name "Manufacturer") "YAGEO(国巨)")
      )
      (libsource (lib "") (part "CC0603KRX7R8BB104"))
    )
    (comp (ref "C55")
      (value "100nF")
      (fields
        (field (name "Manufacturer Part") "CC0603KRX7R8BB104")
        (field (name "Manufacturer") "YAGEO(国巨)")
      )
      (libsource (lib "") (part "CC0603KRX7R8BB104"))
    )
    (comp (ref "C56")
      (value "100nF")
      (fields
        (field (name "Manufacturer Part") "CC0603KRX7R8BB104")
        (field (name "Manufacturer") "YAGEO(国巨)")
      )
      (libsource (lib "") (part "CC0603KRX7R8BB104"))
    )
    (comp (ref "C57")
      (value "100nF")
      (fields
        (field (name "Manufacturer Part") "CC0603KRX7R8BB104")
        (field (name "Manufacturer") "YAGEO(国巨)")
      )
      (libsource (lib "") (part "CC0603KRX7R8BB104"))
    )
    (comp (ref "C58")
      (value "100nF")
      (fields
        (field (name "Manufacturer Part") "CC0603KRX7R8BB104")
        (field (name "Manufacturer") "YAGEO(国巨)")
      )
      (libsource (lib "") (part "CC0603KRX7R8BB104"))
    )
    (comp (ref "C59")
      (value "100nF")
      (fields
        (field (name "Manufacturer Part") "CC0603KRX7R8BB104")
        (field (name "Manufacturer") "YAGEO(国巨)")
      )
      (libsource (lib "") (part "CC0603KRX7R8BB104"))
    )
    (comp (ref "C60")
      (value "100nF")
      (fields
        (field (name "Manufacturer Part") "CC0603KRX7R8BB104")
        (field (name "Manufacturer") "YAGEO(国巨)")
      )
      (libsource (lib "") (part "CC0603KRX7R8BB104"))
    )
    (comp (ref "C61")
      (value "100nF")
      (fields
        (field (name "Manufacturer Part") "CC0603KRX7R8BB104")
        (field (name "Manufacturer") "YAGEO(国巨)")
      )
      (libsource (lib "") (part "CC0603KRX7R8BB104"))
    )
    (comp (ref "C62")
      (value "100nF")
      (fields
        (field (name "Manufacturer Part") "CC0603KRX7R8BB104")
        (field (name "Manufacturer") "YAGEO(国巨)")
      )
      (libsource (lib "") (part "CC0603KRX7R8BB104"))
    )
    (comp (ref "C63")
      (value "100nF")
      (fields
        (field (name "Manufacturer Part") "CC0603KRX7R8BB104")
        (field (name "Manufacturer") "YAGEO(国巨)")
      )
      (libsource (lib "") (part "CC0603KRX7R8BB104"))
    )
    (comp (ref "C64")
      (value "100nF")
      (fields
        (field (name "Manufacturer Part") "CC0603KRX7R8BB104")
        (field (name "Manufacturer") "YAGEO(国巨)")
      )
      (libsource (lib "") (part "CC0603KRX7R8BB104"))
    )
    (comp (ref "C65")
      (value "100nF")
      (fields
        (field (name "Manufacturer Part") "CC0603KRX7R8BB104")
        (field (name "Manufacturer") "YAGEO(国巨)")
      )
      (libsource (lib "") (part "CC0603KRX7R8BB104"))
    )
    (comp (ref "C66")
      (value "100nF")
      (fields
        (field (name "Manufacturer Part") "CC0603KRX7R8BB104")
        (field (name "Manufacturer") "YAGEO(国巨)")
      )
      (libsource (lib "") (part "CC0603KRX7R8BB104"))
    )
    (comp (ref "C67")
      (value "100nF")
      (fields
        (field (name "Manufacturer Part") "CC0603KRX7R8BB104")
        (field (name "Manufacturer") "YAGEO(国巨)")
      )
      (libsource (lib "") (part "CC0603KRX7R8BB104"))
    )
    (comp (ref "C68")
      (value "100nF")
      (fields
        (field (name "Manufacturer Part") "CC0603KRX7R8BB104")
        (field (name "Manufacturer") "YAGEO(国巨)")
      )
      (libsource (lib "") (part "CC0603KRX7R8BB104"))
    )
    (comp (ref "C69")
      (value "100nF")
      (fields
        (field (name "Manufacturer Part") "CC0603KRX7R8BB104")
        (field (name "Manufacturer") "YAGEO(国巨)")
      )
      (libsource (lib "") (part "CC0603KRX7R8BB104"))
    )
    (comp (ref "C70")
      (value "100nF")
      (fields
        (field (name "Manufacturer Part") "CC0603KRX7R8BB104")
        (field (name "Manufacturer") "YAGEO(国巨)")
      )
      (libsource (lib "") (part "CC0603KRX7R8BB104"))
    )
    (comp (ref "C71")
      (value "100nF")
      (fields
        (field (name "Manufacturer Part") "CC0603KRX7R8BB104")
        (field (name "Manufacturer") "YAGEO(国巨)")
      )
      (libsource (lib "") (part "CC0603KRX7R8BB104"))
    )
    (comp (ref "C72")
      (value "100nF")
      (fields
        (field (name "Manufacturer Part") "CC0603KRX7R8BB104")
        (field (name "Manufacturer") "YAGEO(国巨)")
      )
      (libsource (lib "") (part "CC0603KRX7R8BB104"))
    )
    (comp (ref "C73")
      (value "100nF")
      (fields
        (field (name "Manufacturer Part") "CC0603KRX7R8BB104")
        (field (name "Manufacturer") "YAGEO(国巨)")
      )
      (libsource (lib "") (part "CC0603KRX7R8BB104"))
    )
    (comp (ref "C74")
      (value "100nF")
      (fields
        (field (name "Manufacturer Part") "CC0603KRX7R8BB104")
        (field (name "Manufacturer") "YAGEO(国巨)")
      )
      (libsource (lib "") (part "CC0603KRX7R8BB104"))
    )
    (comp (ref "C75")
      (value "100nF")
      (fields
        (field (name "Manufacturer Part") "CC0603KRX7R8BB104")
        (field (name "Manufacturer") "YAGEO(国巨)")
      )
      (libsource (lib "") (part "CC0603KRX7R8BB104"))
    )
    (comp (ref "C76")
      (value "100nF")
      (fields
        (field (name "Manufacturer Part") "CC0603KRX7R8BB104")
        (field (name "Manufacturer") "YAGEO(国巨)")
      )
      (libsource (lib "") (part "CC0603KRX7R8BB104"))
    )
    (comp (ref "C77")
      (value "100nF")
      (fields
        (field (name "Manufacturer Part") "CC0603KRX7R8BB104")
        (field (name "Manufacturer") "YAGEO(国巨)")
      )
      (libsource (lib "") (part "CC0603KRX7R8BB104"))
    )
    (comp (ref "LED1")
      (value "WS2812B-B")
      (fields (field (name "Manufacturer Part") "WS2812B-B/W") (field (name "Manufacturer") "worldsemi"))
      (libsource (lib "") (part "WS2812B-B"))
    )
    (comp (ref "LED2")
      (value "WS2812B-B")
      (fields (field (name "Manufacturer Part") "WS2812B-B/W") (field (name "Manufacturer") "worldsemi"))
      (libsource (lib "") (part "WS2812B-B"))
    )
    (comp (ref "LED3")
      (value "WS2812B-B")
      (fields (field (name "Manufacturer Part") "WS2812B-B/W") (field (name "Manufacturer") "worldsemi"))
      (libsource (lib "") (part "WS2812B-B"))
    )
    (comp (ref "LED4")
      (value "WS2812B-B")
      (fields (field (name "Manufacturer Part") "WS2812B-B/W") (field (name "Manufacturer") "worldsemi"))
      (libsource (lib "") (part "WS2812B-B"))
    )
    (comp (ref "LED5")
      (value "WS2812B-B")
      (fields (field (name "Manufacturer Part") "WS2812B-B/W") (field (name "Manufacturer") "worldsemi"))
      (libsource (lib "") (part "WS2812B-B"))
    )
    (comp (ref "LED6")
      (value "WS2812B-B")
      (fields (field (name "Manufacturer Part") "WS2812B-B/W") (field (name "Manufacturer") "worldsemi"))
      (libsource (lib "") (part "WS2812B-B"))
    )
    (comp (ref "LED7")
      (value "WS2812B-B")
      (fields (field (name "Manufacturer Part") "WS2812B-B/W") (field (name "Manufacturer") "worldsemi"))
      (libsource (lib "") (part "WS2812B-B"))
    )
    (comp (ref "LED8")
      (value "WS2812B-B")
      (fields (field (name "Manufacturer Part") "WS2812B-B/W") (field (name "Manufacturer") "worldsemi"))
      (libsource (lib "") (part "WS2812B-B"))
    )
    (comp (ref "LED9")
      (value "WS2812B-B")
      (fields (field (name "Manufacturer Part") "WS2812B-B/W") (field (name "Manufacturer") "worldsemi"))
      (libsource (lib "") (part "WS2812B-B"))
    )
    (comp (ref "LED10")
      (value "WS2812B-B")
      (fields (field (name "Manufacturer Part") "WS2812B-B/W") (field (name "Manufacturer") "worldsemi"))
      (libsource (lib "") (part "WS2812B-B"))
    )
    (comp (ref "LED11")
      (value "WS2812B-B")
      (fields (field (name "Manufacturer Part") "WS2812B-B/W") (field (name "Manufacturer") "worldsemi"))
      (libsource (lib "") (part "WS2812B-B"))
    )
    (comp (ref "LED12")
      (value "WS2812B-B")
      (fields (field (name "Manufacturer Part") "WS2812B-B/W") (field (name "Manufacturer") "worldsemi"))
      (libsource (lib "") (part "WS2812B-B"))
    )
    (comp (ref "LED13")
      (value "WS2812B-B")
      (fields (field (name "Manufacturer Part") "WS2812B-B/W") (field (name "Manufacturer") "worldsemi"))
      (libsource (lib "") (part "WS2812B-B"))
    )
    (comp (ref "LED14")
      (value "WS2812B-B")
      (fields (field (name "Manufacturer Part") "WS2812B-B/W") (field (name "Manufacturer") "worldsemi"))
      (libsource (lib "") (part "WS2812B-B"))
    )
    (comp (ref "LED15")
      (value "WS2812B-B")
      (fields (field (name "Manufacturer Part") "WS2812B-B/W") (field (name "Manufacturer") "worldsemi"))
      (libsource (lib "") (part "WS2812B-B"))
    )
    (comp (ref "LED16")
      (value "WS2812B-B")
      (fields (field (name "Manufacturer Part") "WS2812B-B/W") (field (name "Manufacturer") "worldsemi"))
      (libsource (lib "") (part "WS2812B-B"))
    )
    (comp (ref "LED17")
      (value "WS2812B-B")
      (fields (field (name "Manufacturer Part") "WS2812B-B/W") (field (name "Manufacturer") "worldsemi"))
      (libsource (lib "") (part "WS2812B-B"))
    )
    (comp (ref "LED18")
      (value "WS2812B-B")
      (fields (field (name "Manufacturer Part") "WS2812B-B/W") (field (name "Manufacturer") "worldsemi"))
      (libsource (lib "") (part "WS2812B-B"))
    )
    (comp (ref "LED19")
      (value "WS2812B-B")
      (fields (field (name "Manufacturer Part") "WS2812B-B/W") (field (name "Manufacturer") "worldsemi"))
      (libsource (lib "") (part "WS2812B-B"))
    )
    (comp (ref "LED20")
      (value "WS2812B-B")
      (fields (field (name "Manufacturer Part") "WS2812B-B/W") (field (name "Manufacturer") "worldsemi"))
      (libsource (lib "") (part "WS2812B-B"))
    )
    (comp (ref "LED21")
      (value "WS2812B-B")
      (fields (field (name "Manufacturer Part") "WS2812B-B/W") (field (name "Manufacturer") "worldsemi"))
      (libsource (lib "") (part "WS2812B-B"))
    )
    (comp (ref "LED22")
      (value "WS2812B-B")
      (fields (field (name "Manufacturer Part") "WS2812B-B/W") (field (name "Manufacturer") "worldsemi"))
      (libsource (lib "") (part "WS2812B-B"))
    )
    (comp (ref "LED23")
      (value "WS2812B-B")
      (fields (field (name "Manufacturer Part") "WS2812B-B/W") (field (name "Manufacturer") "worldsemi"))
      (libsource (lib "") (part "WS2812B-B"))
    )
    (comp (ref "LED24")
      (value "WS2812B-B")
      (fields (field (name "Manufacturer Part") "WS2812B-B/W") (field (name "Manufacturer") "worldsemi"))
      (libsource (lib "") (part "WS2812B-B"))
    )
    (comp (ref "LED25")
      (value "WS2812B-B")
      (fields (field (name "Manufacturer Part") "WS2812B-B/W") (field (name "Manufacturer") "worldsemi"))
      (libsource (lib "") (part "WS2812B-B"))
    )
    (comp (ref "LED26")
      (value "WS2812B-B")
      (fields (field (name "Manufacturer Part") "WS2812B-B/W") (field (name "Manufacturer") "worldsemi"))
      (libsource (lib "") (part "WS2812B-B"))
    )
    (comp (ref "LED27")
      (value "WS2812B-B")
      (fields (field (name "Manufacturer Part") "WS2812B-B/W") (field (name "Manufacturer") "worldsemi"))
      (libsource (lib "") (part "WS2812B-B"))
    )
    (comp (ref "LED28")
      (value "WS2812B-B")
      (fields (field (name "Manufacturer Part") "WS2812B-B/W") (field (name "Manufacturer") "worldsemi"))
      (libsource (lib "") (part "WS2812B-B"))
    )
    (comp (ref "LED29")
      (value "WS2812B-B")
      (fields (field (name "Manufacturer Part") "WS2812B-B/W") (field (name "Manufacturer") "worldsemi"))
      (libsource (lib "") (part "WS2812B-B"))
    )
    (comp (ref "LED30")
      (value "WS2812B-B")
      (fields (field (name "Manufacturer Part") "WS2812B-B/W") (field (name "Manufacturer") "worldsemi"))
      (libsource (lib "") (part "WS2812B-B"))
    )
    (comp (ref "LED31")
      (value "WS2812B-B")
      (fields (field (name "Manufacturer Part") "WS2812B-B/W") (field (name "Manufacturer") "worldsemi"))
      (libsource (lib "") (part "WS2812B-B"))
    )
    (comp (ref "LED32")
      (value "WS2812B-B")
      (fields (field (name "Manufacturer Part") "WS2812B-B/W") (field (name "Manufacturer") "worldsemi"))
      (libsource (lib "") (part "WS2812B-B"))
    )
    (comp (ref "LED33")
      (value "WS2812B-B")
      (fields (field (name "Manufacturer Part") "WS2812B-B/W") (field (name "Manufacturer") "worldsemi"))
      (libsource (lib "") (part "WS2812B-B"))
    )
    (comp (ref "LED34")
      (value "WS2812B-B")
      (fields (field (name "Manufacturer Part") "WS2812B-B/W") (field (name "Manufacturer") "worldsemi"))
      (libsource (lib "") (part "WS2812B-B"))
    )
    (comp (ref "LED35")
      (value "WS2812B-B")
      (fields (field (name "Manufacturer Part") "WS2812B-B/W") (field (name "Manufacturer") "worldsemi"))
      (libsource (lib "") (part "WS2812B-B"))
    )
    (comp (ref "LED36")
      (value "WS2812B-B")
      (fields (field (name "Manufacturer Part") "WS2812B-B/W") (field (name "Manufacturer") "worldsemi"))
      (libsource (lib "") (part "WS2812B-B"))
    )
    (comp (ref "LED37")
      (value "WS2812B-B")
      (fields (field (name "Manufacturer Part") "WS2812B-B/W") (field (name "Manufacturer") "worldsemi"))
      (libsource (lib "") (part "WS2812B-B"))
    )
    (comp (ref "LED38")
      (value "WS2812B-B")
      (fields (field (name "Manufacturer Part") "WS2812B-B/W") (field (name "Manufacturer") "worldsemi"))
      (libsource (lib "") (part "WS2812B-B"))
    )
    (comp (ref "LED39")
      (value "WS2812B-B")
      (fields (field (name "Manufacturer Part") "WS2812B-B/W") (field (name "Manufacturer") "worldsemi"))
      (libsource (lib "") (part "WS2812B-B"))
    )
    (comp (ref "LED40")
      (value "WS2812B-B")
      (fields (field (name "Manufacturer Part") "WS2812B-B/W") (field (name "Manufacturer") "worldsemi"))
      (libsource (lib "") (part "WS2812B-B"))
    )
    (comp (ref "LED41")
      (value "WS2812B-B")
      (fields (field (name "Manufacturer Part") "WS2812B-B/W") (field (name "Manufacturer") "worldsemi"))
      (libsource (lib "") (part "WS2812B-B"))
    )
    (comp (ref "LED42")
      (value "WS2812B-B")
      (fields (field (name "Manufacturer Part") "WS2812B-B/W") (field (name "Manufacturer") "worldsemi"))
      (libsource (lib "") (part "WS2812B-B"))
    )
    (comp (ref "LED43")
      (value "WS2812B-B")
      (fields (field (name "Manufacturer Part") "WS2812B-B/W") (field (name "Manufacturer") "worldsemi"))
      (libsource (lib "") (part "WS2812B-B"))
    )
    (comp (ref "LED44")
      (value "WS2812B-B")
      (fields (field (name "Manufacturer Part") "WS2812B-B/W") (field (name "Manufacturer") "worldsemi"))
      (libsource (lib "") (part "WS2812B-B"))
    )
    (comp (ref "LED45")
      (value "WS2812B-B")
      (fields (field (name "Manufacturer Part") "WS2812B-B/W") (field (name "Manufacturer") "worldsemi"))
      (libsource (lib "") (part "WS2812B-B"))
    )
    (comp (ref "LED46")
      (value "WS2812B-B")
      (fields (field (name "Manufacturer Part") "WS2812B-B/W") (field (name "Manufacturer") "worldsemi"))
      (libsource (lib "") (part "WS2812B-B"))
    )
    (comp (ref "LED47")
      (value "WS2812B-B")
      (fields (field (name "Manufacturer Part") "WS2812B-B/W") (field (name "Manufacturer") "worldsemi"))
      (libsource (lib "") (part "WS2812B-B"))
    )
    (comp (ref "LED48")
      (value "WS2812B-B")
      (fields (field (name "Manufacturer Part") "WS2812B-B/W") (field (name "Manufacturer") "worldsemi"))
      (libsource (lib "") (part "WS2812B-B"))
    )
    (comp (ref "LED49")
      (value "WS2812B-B")
      (fields (field (name "Manufacturer Part") "WS2812B-B/W") (field (name "Manufacturer") "worldsemi"))
      (libsource (lib "") (part "WS2812B-B"))
    )
    (comp (ref "LED50")
      (value "WS2812B-B")
      (fields (field (name "Manufacturer Part") "WS2812B-B/W") (field (name "Manufacturer") "worldsemi"))
      (libsource (lib "") (part "WS2812B-B"))
    )
    (comp (ref "LED51")
      (value "WS2812B-B")
      (fields (field (name "Manufacturer Part") "WS2812B-B/W") (field (name "Manufacturer") "worldsemi"))
      (libsource (lib "") (part "WS2812B-B"))
    )
    (comp (ref "LED52")
      (value "WS2812B-B")
      (fields (field (name "Manufacturer Part") "WS2812B-B/W") (field (name "Manufacturer") "worldsemi"))
      (libsource (lib "") (part "WS2812B-B"))
    )
    (comp (ref "LED53")
      (value "WS2812B-B")
      (fields (field (name "Manufacturer Part") "WS2812B-B/W") (field (name "Manufacturer") "worldsemi"))
      (libsource (lib "") (part "WS2812B-B"))
    )
    (comp (ref "LED54")
      (value "WS2812B-B")
      (fields (field (name "Manufacturer Part") "WS2812B-B/W") (field (name "Manufacturer") "worldsemi"))
      (libsource (lib "") (part "WS2812B-B"))
    )
    (comp (ref "LED55")
      (value "WS2812B-B")
      (fields (field (name "Manufacturer Part") "WS2812B-B/W") (field (name "Manufacturer") "worldsemi"))
      (libsource (lib "") (part "WS2812B-B"))
    )
    (comp (ref "LED56")
      (value "WS2812B-B")
      (fields (field (name "Manufacturer Part") "WS2812B-B/W") (field (name "Manufacturer") "worldsemi"))
      (libsource (lib "") (part "WS2812B-B"))
    )
    (comp (ref "LED57")
      (value "WS2812B-B")
      (fields (field (name "Manufacturer Part") "WS2812B-B/W") (field (name "Manufacturer") "worldsemi"))
      (libsource (lib "") (part "WS2812B-B"))
    )
    (comp (ref "LED58")
      (value "WS2812B-B")
      (fields (field (name "Manufacturer Part") "WS2812B-B/W") (field (name "Manufacturer") "worldsemi"))
      (libsource (lib "") (part "WS2812B-B"))
    )
    (comp (ref "LED59")
      (value "WS2812B-B")
      (fields (field (name "Manufacturer Part") "WS2812B-B/W") (field (name "Manufacturer") "worldsemi"))
      (libsource (lib "") (part "WS2812B-B"))
    )
    (comp (ref "LED60")
      (value "WS2812B-B")
      (fields (field (name "Manufacturer Part") "WS2812B-B/W") (field (name "Manufacturer") "worldsemi"))
      (libsource (lib "") (part "WS2812B-B"))
    )
    (comp (ref "LED61")
      (value "WS2812B-B")
      (fields (field (name "Manufacturer Part") "WS2812B-B/W") (field (name "Manufacturer") "worldsemi"))
      (libsource (lib "") (part "WS2812B-B"))
    )
    (comp (ref "LED62")
      (value "WS2812B-B")
      (fields (field (name "Manufacturer Part") "WS2812B-B/W") (field (name "Manufacturer") "worldsemi"))
      (libsource (lib "") (part "WS2812B-B"))
    )
    (comp (ref "LED63")
      (value "WS2812B-B")
      (fields (field (name "Manufacturer Part") "WS2812B-B/W") (field (name "Manufacturer") "worldsemi"))
      (libsource (lib "") (part "WS2812B-B"))
    )
    (comp (ref "LED64")
      (value "WS2812B-B")
      (fields (field (name "Manufacturer Part") "WS2812B-B/W") (field (name "Manufacturer") "worldsemi"))
      (libsource (lib "") (part "WS2812B-B"))
    )
  )
  (nets
    (net (code "1") (name "+5V") (class "Default")
      (node (ref "C14") (pin "2") (pinfunction "2_2") (pintype "input"))
      (node (ref "C15") (pin "2") (pinfunction "2_2") (pintype "input"))
      (node (ref "C16") (pin "2") (pinfunction "2_2") (pintype "input"))
      (node (ref "C17") (pin "2") (pinfunction "2_2") (pintype "input"))
      (node (ref "C18") (pin "2") (pinfunction "2_2") (pintype "input"))
      (node (ref "C19") (pin "2") (pinfunction "2_2") (pintype "input"))
      (node (ref "C20") (pin "2") (pinfunction "2_2") (pintype "input"))
      (node (ref "C21") (pin "2") (pinfunction "2_2") (pintype "input"))
      (node (ref "C22") (pin "2") (pinfunction "2_2") (pintype "input"))
      (node (ref "C23") (pin "2") (pinfunction "2_2") (pintype "input"))
      (node (ref "C24") (pin "2") (pinfunction "2_2") (pintype "input"))
      (node (ref "C25") (pin "2") (pinfunction "2_2") (pintype "input"))
      (node (ref "C26") (pin "2") (pinfunction "2_2") (pintype "input"))
      (node (ref "C27") (pin "2") (pinfunction "2_2") (pintype "input"))
      (node (ref "C28") (pin "2") (pinfunction "2_2") (pintype "input"))
      (node (ref "C29") (pin "2") (pinfunction "2_2") (pintype "input"))
      (node (ref "C30") (pin "2") (pinfunction "2_2") (pintype "input"))
      (node (ref "C31") (pin "2") (pinfunction "2_2") (pintype "input"))
      (node (ref "C32") (pin "2") (pinfunction "2_2") (pintype "input"))
      (node (ref "C33") (pin "2") (pinfunction "2_2") (pintype "input"))
      (node (ref "C34") (pin "2") (pinfunction "2_2") (pintype "input"))
      (node (ref "C35") (pin "2") (pinfunction "2_2") (pintype "input"))
      (node (ref "C36") (pin "2") (pinfunction "2_2") (pintype "input"))
      (node (ref "C37") (pin "2") (pinfunction "2_2") (pintype "input"))
      (node (ref "C38") (pin "2") (pinfunction "2_2") (pintype "input"))
      (node (ref "C39") (pin "2") (pinfunction "2_2") (pintype "input"))
      (node (ref "C40") (pin "2") (pinfunction "2_2") (pintype "input"))
      (node (ref "C41") (pin "2") (pinfunction "2_2") (pintype "input"))
      (node (ref "C42") (pin "2") (pinfunction "2_2") (pintype "input"))
      (node (ref "C43") (pin "2") (pinfunction "2_2") (pintype "input"))
      (node (ref "C44") (pin "2") (pinfunction "2_2") (pintype "input"))
      (node (ref "C45") (pin "2") (pinfunction "2_2") (pintype "input"))
      (node (ref "C46") (pin "2") (pinfunction "2_2") (pintype "input"))
      (node (ref "C47") (pin "2") (pinfunction "2_2") (pintype "input"))
      (node (ref "C48") (pin "2") (pinfunction "2_2") (pintype "input"))
      (node (ref "C49") (pin "2") (pinfunction "2_2") (pintype "input"))
      (node (ref "C50") (pin "2") (pinfunction "2_2") (pintype "input"))
      (node (ref "C51") (pin "2") (pinfunction "2_2") (pintype "input"))
      (node (ref "C52") (pin "2") (pinfunction "2_2") (pintype "input"))
      (node (ref "C53") (pin "2") (pinfunction "2_2") (pintype "input"))
      (node (ref "C54") (pin "2") (pinfunction "2_2") (pintype "input"))
      (node (ref "C55") (pin "2") (pinfunction "2_2") (pintype "input"))
      (node (ref "C56") (pin "2") (pinfunction "2_2") (pintype "input"))
      (node (ref "C57") (pin "2") (pinfunction "2_2") (pintype "input"))
      (node (ref "C58") (pin "2") (pinfunction "2_2") (pintype "input"))
      (node (ref "C59") (pin "2") (pinfunction "2_2") (pintype "input"))
      (node (ref "C60") (pin "2") (pinfunction "2_2") (pintype "input"))
      (node (ref "C61") (pin "2") (pinfunction "2_2") (pintype "input"))
      (node (ref "C62") (pin "2") (pinfunction "2_2") (pintype "input"))
      (node (ref "C63") (pin "2") (pinfunction "2_2") (pintype "input"))
      (node (ref "C64") (pin "2") (pinfunction "2_2") (pintype "input"))
      (node (ref "C65") (pin "2") (pinfunction "2_2") (pintype "input"))
      (node (ref "C66") (pin "2") (pinfunction "2_2") (pintype "input"))
      (node (ref "C67") (pin "2") (pinfunction "2_2") (pintype "input"))
      (node (ref "C68") (pin "2") (pinfunction "2_2") (pintype "input"))
      (node (ref "C69") (pin "2") (pinfunction "2_2") (pintype "input"))
      (node (ref "C70") (pin "2") (pinfunction "2_2") (pintype "input"))
      (node (ref "C71") (pin "2") (pinfunction "2_2") (pintype "input"))
      (node (ref "C72") (pin "2") (pinfunction "2_2") (pintype "input"))
      (node (ref "C73") (pin "2") (pinfunction "2_2") (pintype "input"))
      (node (ref "C74") (pin "2") (pinfunction "2_2") (pintype "input"))
      (node (ref "C75") (pin "2") (pinfunction "2_2") (pintype "input"))
      (node (ref "C76") (pin "2") (pinfunction "2_2") (pintype "input"))
      (node (ref "C77") (pin "2") (pinfunction "2_2") (pintype "input"))
      (node (ref "LED1") (pin "1") (pinfunction "VDD_1") (pintype "unspecified"))
      (node (ref "LED10") (pin "1") (pinfunction "VDD_1") (pintype "unspecified"))
      (node (ref "LED11") (pin "1") (pinfunction "VDD_1") (pintype "unspecified"))
      (node (ref "LED12") (pin "1") (pinfunction "VDD_1") (pintype "unspecified"))
      (node (ref "LED13") (pin "1") (pinfunction "VDD_1") (pintype "unspecified"))
      (node (ref "LED14") (pin "1") (pinfunction "VDD_1") (pintype "unspecified"))
      (node (ref "LED15") (pin "1") (pinfunction "VDD_1") (pintype "unspecified"))
      (node (ref "LED16") (pin "1") (pinfunction "VDD_1") (pintype "unspecified"))
      (node (ref "LED17") (pin "1") (pinfunction "VDD_1") (pintype "unspecified"))
      (node (ref "LED18") (pin "1") (pinfunction "VDD_1") (pintype "unspecified"))
      (node (ref "LED19") (pin "1") (pinfunction "VDD_1") (pintype "unspecified"))
      (node (ref "LED2") (pin "1") (pinfunction "VDD_1") (pintype "unspecified"))
      (node (ref "LED20") (pin "1") (pinfunction "VDD_1") (pintype "unspecified"))
      (node (ref "LED21") (pin "1") (pinfunction "VDD_1") (pintype "unspecified"))
      (node (ref "LED22") (pin "1") (pinfunction "VDD_1") (pintype "unspecified"))
      (node (ref "LED23") (pin "1") (pinfunction "VDD_1") (pintype "unspecified"))
      (node (ref "LED24") (pin "1") (pinfunction "VDD_1") (pintype "unspecified"))
      (node (ref "LED25") (pin "1") (pinfunction "VDD_1") (pintype "unspecified"))
      (node (ref "LED26") (pin "1") (pinfunction "VDD_1") (pintype "unspecified"))
      (node (ref "LED27") (pin "1") (pinfunction "VDD_1") (pintype "unspecified"))
      (node (ref "LED28") (pin "1") (pinfunction "VDD_1") (pintype "unspecified"))
      (node (ref "LED29") (pin "1") (pinfunction "VDD_1") (pintype "unspecified"))
      (node (ref "LED3") (pin "1") (pinfunction "VDD_1") (pintype "unspecified"))
      (node (ref "LED30") (pin "1") (pinfunction "VDD_1") (pintype "unspecified"))
      (node (ref "LED31") (pin "1") (pinfunction "VDD_1") (pintype "unspecified"))
      (node (ref "LED32") (pin "1") (pinfunction "VDD_1") (pintype "unspecified"))
      (node (ref "LED33") (pin "1") (pinfunction "VDD_1") (pintype "unspecified"))
      (node (ref "LED34") (pin "1") (pinfunction "VDD_1") (pintype "unspecified"))
      (node (ref "LED35") (pin "1") (pinfunction "VDD_1") (pintype "unspecified"))
      (node (ref "LED36") (pin "1") (pinfunction "VDD_1") (pintype "unspecified"))
      (node (ref "LED37") (pin "1") (pinfunction "VDD_1") (pintype "unspecified"))
      (node (ref "LED38") (pin "1") (pinfunction "VDD_1") (pintype "unspecified"))
      (node (ref "LED39") (pin "1") (pinfunction "VDD_1") (pintype "unspecified"))
      (node (ref "LED4") (pin "1") (pinfunction "VDD_1") (pintype "unspecified"))
      (node (ref "LED40") (pin "1") (pinfunction "VDD_1") (pintype "unspecified"))
      (node (ref "LED41") (pin "1") (pinfunction "VDD_1") (pintype "unspecified"))
      (node (ref "LED42") (pin "1") (pinfunction "VDD_1") (pintype "unspecified"))
      (node (ref "LED43") (pin "1") (pinfunction "VDD_1") (pintype "unspecified"))
      (node (ref "LED44") (pin "1") (pinfunction "VDD_1") (pintype "unspecified"))
      (node (ref "LED45") (pin "1") (pinfunction "VDD_1") (pintype "unspecified"))
      (node (ref "LED46") (pin "1") (pinfunction "VDD_1") (pintype "unspecified"))
      (node (ref "LED47") (pin "1") (pinfunction "VDD_1") (pintype "unspecified"))
      (node (ref "LED48") (pin "1") (pinfunction "VDD_1") (pintype "unspecified"))
      (node (ref "LED49") (pin "1") (pinfunction "VDD_1") (pintype "unspecified"))
      (node (ref "LED5") (pin "1") (pinfunction "VDD_1") (pintype "unspecified"))
      (node (ref "LED50") (pin "1") (pinfunction "VDD_1") (pintype "unspecified"))
      (node (ref "LED51") (pin "1") (pinfunction "VDD_1") (pintype "unspecified"))
      (node (ref "LED52") (pin "1") (pinfunction "VDD_1") (pintype "unspecified"))
      (node (ref "LED53") (pin "1") (pinfunction "VDD_1") (pintype "unspecified"))
      (node (ref "LED54") (pin "1") (pinfunction "VDD_1") (pintype "unspecified"))
      (node (ref "LED55") (pin "1") (pinfunction "VDD_1") (pintype "unspecified"))
      (node (ref "LED56") (pin "1") (pinfunction "VDD_1") (pintype "unspecified"))
      (node (ref "LED57") (pin "1") (pinfunction "VDD_1") (pintype "unspecified"))
      (node (ref "LED58") (pin "1") (pinfunction "VDD_1") (pintype "unspecified"))
      (node (ref "LED59") (pin "1") (pinfunction "VDD_1") (pintype "unspecified"))
      (node (ref "LED6") (pin "1") (pinfunction "VDD_1") (pintype "unspecified"))
      (node (ref "LED60") (pin "1") (pinfunction "VDD_1") (pintype "unspecified"))
      (node (ref "LED61") (pin "1") (pinfunction "VDD_1") (pintype "unspecified"))
      (node (ref "LED62") (pin "1") (pinfunction "VDD_1") (pintype "unspecified"))
      (node (ref "LED63") (pin "1") (pinfunction "VDD_1") (pintype "unspecified"))
      (node (ref "LED64") (pin "1") (pinfunction "VDD_1") (pintype "unspecified"))
      (node (ref "LED7") (pin "1") (pinfunction "VDD_1") (pintype "unspecified"))
      (node (ref "LED8") (pin "1") (pinfunction "VDD_1") (pintype "unspecified"))
      (node (ref "LED9") (pin "1") (pinfunction "VDD_1") (pintype "unspecified"))
    )
    (net (code "2") (name "GND") (class "Default")
      (node (ref "C14") (pin "1") (pinfunction "1_1") (pintype "input"))
      (node (ref "C15") (pin "1") (pinfunction "1_1") (pintype "input"))
      (node (ref "C16") (pin "1") (pinfunction "1_1") (pintype "input"))
      (node (ref "C17") (pin "1") (pinfunction "1_1") (pintype "input"))
      (node (ref "C18") (pin "1") (pinfunction "1_1") (pintype "input"))
      (node (ref "C19") (pin "1") (pinfunction "1_1") (pintype "input"))
      (node (ref "C20") (pin "1") (pinfunction "1_1") (pintype "input"))
      (node (ref "C21") (pin "1") (pinfunction "1_1") (pintype "input"))
      (node (ref "C22") (pin "1") (pinfunction "1_1") (pintype "input"))
      (node (ref "C23") (pin "1") (pinfunction "1_1") (pintype "input"))
      (node (ref "C24") (pin "1") (pinfunction "1_1") (pintype "input"))
      (node (ref "C25") (pin "1") (pinfunction "1_1") (pintype "input"))
      (node (ref "C26") (pin "1") (pinfunction "1_1") (pintype "input"))
      (node (ref "C27") (pin "1") (pinfunction "1_1") (pintype "input"))
      (node (ref "C28") (pin "1") (pinfunction "1_1") (pintype "input"))
      (node (ref "C29") (pin "1") (pinfunction "1_1") (pintype "input"))
      (node (ref "C30") (pin "1") (pinfunction "1_1") (pintype "input"))
      (node (ref "C31") (pin "1") (pinfunction "1_1") (pintype "input"))
      (node (ref "C32") (pin "1") (pinfunction "1_1") (pintype "input"))
      (node (ref "C33") (pin "1") (pinfunction "1_1") (pintype "input"))
      (node (ref "C34") (pin "1") (pinfunction "1_1") (pintype "input"))
      (node (ref "C35") (pin "1") (pinfunction "1_1") (pintype "input"))
      (node (ref "C36") (pin "1") (pinfunction "1_1") (pintype "input"))
      (node (ref "C37") (pin "1") (pinfunction "1_1") (pintype "input"))
      (node (ref "C38") (pin "1") (pinfunction "1_1") (pintype "input"))
      (node (ref "C39") (pin "1") (pinfunction "1_1") (pintype "input"))
      (node (ref "C40") (pin "1") (pinfunction "1_1") (pintype "input"))
      (node (ref "C41") (pin "1") (pinfunction "1_1") (pintype "input"))
      (node (ref "C42") (pin "1") (pinfunction "1_1") (pintype "input"))
      (node (ref "C43") (pin "1") (pinfunction "1_1") (pintype "input"))
      (node (ref "C44") (pin "1") (pinfunction "1_1") (pintype "input"))
      (node (ref "C45") (pin "1") (pinfunction "1_1") (pintype "input"))
      (node (ref "C46") (pin "1") (pinfunction "1_1") (pintype "input"))
      (node (ref "C47") (pin "1") (pinfunction "1_1") (pintype "input"))
      (node (ref "C48") (pin "1") (pinfunction "1_1") (pintype "input"))
      (node (ref "C49") (pin "1") (pinfunction "1_1") (pintype "input"))
      (node (ref "C50") (pin "1") (pinfunction "1_1") (pintype "input"))
      (node (ref "C51") (pin "1") (pinfunction "1_1") (pintype "input"))
      (node (ref "C52") (pin "1") (pinfunction "1_1") (pintype "input"))
      (node (ref "C53") (pin "1") (pinfunction "1_1") (pintype "input"))
      (node (ref "C54") (pin "1") (pinfunction "1_1") (pintype "input"))
      (node (ref "C55") (pin "1") (pinfunction "1_1") (pintype "input"))
      (node (ref "C56") (pin "1") (pinfunction "1_1") (pintype "input"))
      (node (ref "C57") (pin "1") (pinfunction "1_1") (pintype "input"))
      (node (ref "C58") (pin "1") (pinfunction "1_1") (pintype "input"))
      (node (ref "C59") (pin "1") (pinfunction "1_1") (pintype "input"))
      (node (ref "C60") (pin "1") (pinfunction "1_1") (pintype "input"))
      (node (ref "C61") (pin "1") (pinfunction "1_1") (pintype "input"))
      (node (ref "C62") (pin "1") (pinfunction "1_1") (pintype "input"))
      (node (ref "C63") (pin "1") (pinfunction "1_1") (pintype "input"))
      (node (ref "C64") (pin "1") (pinfunction "1_1") (pintype "input"))
      (node (ref "C65") (pin "1") (pinfunction "1_1") (pintype "input"))
      (node (ref "C66") (pin "1") (pinfunction "1_1") (pintype "input"))
      (node (ref "C67") (pin "1") (pinfunction "1_1") (pintype "input"))
      (node (ref "C68") (pin "1") (pinfunction "1_1") (pintype "input"))
      (node (ref "C69") (pin "1") (pinfunction "1_1") (pintype "input"))
      (node (ref "C70") (pin "1") (pinfunction "1_1") (pintype "input"))
      (node (ref "C71") (pin "1") (pinfunction "1_1") (pintype "input"))
      (node (ref "C72") (pin "1") (pinfunction "1_1") (pintype "input"))
      (node (ref "C73") (pin "1") (pinfunction "1_1") (pintype "input"))
      (node (ref "C74") (pin "1") (pinfunction "1_1") (pintype "input"))
      (node (ref "C75") (pin "1") (pinfunction "1_1") (pintype "input"))
      (node (ref "C76") (pin "1") (pinfunction "1_1") (pintype "input"))
      (node (ref "C77") (pin "1") (pinfunction "1_1") (pintype "input"))
      (node (ref "LED1") (pin "3") (pinfunction "VSS_3") (pintype "unspecified"))
      (node (ref "LED10") (pin "3") (pinfunction "VSS_3") (pintype "unspecified"))
      (node (ref "LED11") (pin "3") (pinfunction "VSS_3") (pintype "unspecified"))
      (node (ref "LED12") (pin "3") (pinfunction "VSS_3") (pintype "unspecified"))
      (node (ref "LED13") (pin "3") (pinfunction "VSS_3") (pintype "unspecified"))
      (node (ref "LED14") (pin "3") (pinfunction "VSS_3") (pintype "unspecified"))
      (node (ref "LED15") (pin "3") (pinfunction "VSS_3") (pintype "unspecified"))
      (node (ref "LED16") (pin "3") (pinfunction "VSS_3") (pintype "unspecified"))
      (node (ref "LED17") (pin "3") (pinfunction "VSS_3") (pintype "unspecified"))
      (node (ref "LED18") (pin "3") (pinfunction "VSS_3") (pintype "unspecified"))
      (node (ref "LED19") (pin "3") (pinfunction "VSS_3") (pintype "unspecified"))
      (node (ref "LED2") (pin "3") (pinfunction "VSS_3") (pintype "unspecified"))
      (node (ref "LED20") (pin "3") (pinfunction "VSS_3") (pintype "unspecified"))
      (node (ref "LED21") (pin "3") (pinfunction "VSS_3") (pintype "unspecified"))
      (node (ref "LED22") (pin "3") (pinfunction "VSS_3") (pintype "unspecified"))
      (node (ref "LED23") (pin "3") (pinfunction "VSS_3") (pintype "unspecified"))
      (node (ref "LED24") (pin "3") (pinfunction "VSS_3") (pintype "unspecified"))
      (node (ref "LED25") (pin "3") (pinfunction "VSS_3") (pintype "unspecified"))
      (node (ref "LED26") (pin "3") (pinfunction "VSS_3") (pintype "unspecified"))
      (node (ref "LED27") (pin "3") (pinfunction "VSS_3") (pintype "unspecified"))
      (node (ref "LED28") (pin "3") (pinfunction "VSS_3") (pintype "unspecified"))
      (node (ref "LED29") (pin "3") (pinfunction "VSS_3") (pintype "unspecified"))
      (node (ref "LED3") (pin "3") (pinfunction "VSS_3") (pintype "unspecified"))
      (node (ref "LED30") (pin "3") (pinfunction "VSS_3") (pintype "unspecified"))
      (node (ref "LED31") (pin "3") (pinfunction "VSS_3") (pintype "unspecified"))
      (node (ref "LED32") (pin "3") (pinfunction "VSS_3") (pintype "unspecified"))
      (node (ref "LED33") (pin "3") (pinfunction "VSS_3") (pintype "unspecified"))
      (node (ref "LED34") (pin "3") (pinfunction "VSS_3") (pintype "unspecified"))
      (node (ref "LED35") (pin "3") (pinfunction "VSS_3") (pintype "unspecified"))
      (node (ref "LED36") (pin "3") (pinfunction "VSS_3") (pintype "unspecified"))
      (node (ref "LED37") (pin "3") (pinfunction "VSS_3") (pintype "unspecified"))
      (node (ref "LED38") (pin "3") (pinfunction "VSS_3") (pintype "unspecified"))
      (node (ref "LED39") (pin "3") (pinfunction "VSS_3") (pintype "unspecified"))
      (node (ref "LED4") (pin "3") (pinfunction "VSS_3") (pintype "unspecified"))
      (node (ref "LED40") (pin "3") (pinfunction "VSS_3") (pintype "unspecified"))
      (node (ref "LED41") (pin "3") (pinfunction "VSS_3") (pintype "unspecified"))
      (node (ref "LED42") (pin "3") (pinfunction "VSS_3") (pintype "unspecified"))
      (node (ref "LED43") (pin "3") (pinfunction "VSS_3") (pintype "unspecified"))
      (node (ref "LED44") (pin "3") (pinfunction "VSS_3") (pintype "unspecified"))
      (node (ref "LED45") (pin "3") (pinfunction "VSS_3") (pintype "unspecified"))
      (node (ref "LED46") (pin "3") (pinfunction "VSS_3") (pintype "unspecified"))
      (node (ref "LED47") (pin "3") (pinfunction "VSS_3") (pintype "unspecified"))
      (node (ref "LED48") (pin "3") (pinfunction "VSS_3") (pintype "unspecified"))
      (node (ref "LED49") (pin "3") (pinfunction "VSS_3") (pintype "unspecified"))
      (node (ref "LED5") (pin "3") (pinfunction "VSS_3") (pintype "unspecified"))
      (node (ref "LED50") (pin "3") (pinfunction "VSS_3") (pintype "unspecified"))
      (node (ref "LED51") (pin "3") (pinfunction "VSS_3") (pintype "unspecified"))
      (node (ref "LED52") (pin "3") (pinfunction "VSS_3") (pintype "unspecified"))
      (node (ref "LED53") (pin "3") (pinfunction "VSS_3") (pintype "unspecified"))
      (node (ref "LED54") (pin "3") (pinfunction "VSS_3") (pintype "unspecified"))
      (node (ref "LED55") (pin "3") (pinfunction "VSS_3") (pintype "unspecified"))
      (node (ref "LED56") (pin "3") (pinfunction "VSS_3") (pintype "unspecified"))
      (node (ref "LED57") (pin "3") (pinfunction "VSS_3") (pintype "unspecified"))
      (node (ref "LED58") (pin "3") (pinfunction "VSS_3") (pintype "unspecified"))
      (node (ref "LED59") (pin "3") (pinfunction "VSS_3") (pintype "unspecified"))
      (node (ref "LED6") (pin "3") (pinfunction "VSS_3") (pintype "unspecified"))
      (node (ref "LED60") (pin "3") (pinfunction "VSS_3") (pintype "unspecified"))
      (node (ref "LED61") (pin "3") (pinfunction "VSS_3") (pintype "unspecified"))
      (node (ref "LED62") (pin "3") (pinfunction "VSS_3") (pintype "unspecified"))
      (node (ref "LED63") (pin "3") (pinfunction "VSS_3") (pintype "unspecified"))
      (node (ref "LED64") (pin "3") (pinfunction "VSS_3") (pintype "unspecified"))
      (node (ref "LED7") (pin "3") (pinfunction "VSS_3") (pintype "unspecified"))
      (node (ref "LED8") (pin "3") (pinfunction "VSS_3") (pintype "unspecified"))
      (node (ref "LED9") (pin "3") (pinfunction "VSS_3") (pintype "unspecified"))
    )
    (net (code "3") (name "Key1") (class "Default")
      (node (ref "SW17") (pin "1") (pinfunction "1_1") (pintype "unspecified"))
      (node (ref "SW18") (pin "1") (pinfunction "1_1") (pintype "unspecified"))
      (node (ref "SW2") (pin "1") (pinfunction "1_1") (pintype "unspecified"))
      (node (ref "SW33") (pin "1") (pinfunction "1_1") (pintype "unspecified"))
      (node (ref "SW34") (pin "1") (pinfunction "1_1") (pintype "unspecified"))
      (node (ref "SW49") (pin "1") (pinfunction "1_1") (pintype "unspecified"))
      (node (ref "SW50") (pin "1") (pinfunction "1_1") (pintype "unspecified"))
      (node (ref "SW65") (pin "1") (pinfunction "1_1") (pintype "unspecified"))
    )
    (net (code "4") (name "Key2") (class "Default")
      (node (ref "SW16") (pin "1") (pinfunction "1_1") (pintype "unspecified"))
      (node (ref "SW19") (pin "1") (pinfunction "1_1") (pintype "unspecified"))
      (node (ref "SW3") (pin "1") (pinfunction "1_1") (pintype "unspecified"))
      (node (ref "SW32") (pin "1") (pinfunction "1_1") (pintype "unspecified"))
      (node (ref "SW35") (pin "1") (pinfunction "1_1") (pintype "unspecified"))
      (node (ref "SW48") (pin "1") (pinfunction "1_1") (pintype "unspecified"))
      (node (ref "SW51") (pin "1") (pinfunction "1_1") (pintype "unspecified"))
      (node (ref "SW64") (pin "1") (pinfunction "1_1") (pintype "unspecified"))
    )
    (net (code "5") (name "Key3") (class "Default")
      (node (ref "SW14") (pin "1") (pinfunction "1_1") (pintype "unspecified"))
      (node (ref "SW21") (pin "1") (pinfunction "1_1") (pintype "unspecified"))
      (node (ref "SW30") (pin "1") (pinfunction "1_1") (pintype "unspecified"))
      (node (ref "SW37") (pin "1") (pinfunction "1_1") (pintype "unspecified"))
      (node (ref "SW46") (pin "1") (pinfunction "1_1") (pintype "unspecified"))
      (node (ref "SW5") (pin "1") (pinfunction "1_1") (pintype "unspecified"))
      (node (ref "SW53") (pin "1") (pinfunction "1_1") (pintype "unspecified"))
      (node (ref "SW62") (pin "1") (pinfunction "1_1") (pintype "unspecified"))
    )
    (net (code "6") (name "Key4") (class "Default")
      (node (ref "SW15") (pin "1") (pinfunction "1_1") (pintype "unspecified"))
      (node (ref "SW20") (pin "1") (pinfunction "1_1") (pintype "unspecified"))
      (node (ref "SW31") (pin "1") (pinfunction "1_1") (pintype "unspecified"))
      (node (ref "SW36") (pin "1") (pinfunction "1_1") (pintype "unspecified"))
      (node (ref "SW4") (pin "1") (pinfunction "1_1") (pintype "unspecified"))
      (node (ref "SW47") (pin "1") (pinfunction "1_1") (pintype "unspecified"))
      (node (ref "SW52") (pin "1") (pinfunction "1_1") (pintype "unspecified"))
      (node (ref "SW63") (pin "1") (pinfunction "1_1") (pintype "unspecified"))
    )
    (net (code "7") (name "Key5") (class "Default")
      (node (ref "SW10") (pin "1") (pinfunction "1_1") (pintype "unspecified"))
      (node (ref "SW25") (pin "1") (pinfunction "1_1") (pintype "unspecified"))
      (node (ref "SW26") (pin "1") (pinfunction "1_1") (pintype "unspecified"))
      (node (ref "SW41") (pin "1") (pinfunction "1_1") (pintype "unspecified"))
      (node (ref "SW42") (pin "1") (pinfunction "1_1") (pintype "unspecified"))
      (node (ref "SW57") (pin "1") (pinfunction "1_1") (pintype "unspecified"))
      (node (ref "SW58") (pin "1") (pinfunction "1_1") (pintype "unspecified"))
      (node (ref "SW9") (pin "1") (pinfunction "1_1") (pintype "unspecified"))
    )
    (net (code "8") (name "Key6") (class "Default")
      (node (ref "SW11") (pin "1") (pinfunction "1_1") (pintype "unspecified"))
      (node (ref "SW24") (pin "1") (pinfunction "1_1") (pintype "unspecified"))
      (node (ref "SW27") (pin "1") (pinfunction "1_1") (pintype "unspecified"))
      (node (ref "SW40") (pin "1") (pinfunction "1_1") (pintype "unspecified"))
      (node (ref "SW43") (pin "1") (pinfunction "1_1") (pintype "unspecified"))
      (node (ref "SW56") (pin "1") (pinfunction "1_1") (pintype "unspecified"))
      (node (ref "SW59") (pin "1") (pinfunction "1_1") (pintype "unspecified"))
      (node (ref "SW8") (pin "1") (pinfunction "1_1") (pintype "unspecified"))
    )
    (net (code "9") (name "Key7") (class "Default")
      (node (ref "SW13") (pin "1") (pinfunction "1_1") (pintype "unspecified"))
      (node (ref "SW22") (pin "1") (pinfunction "1_1") (pintype "unspecified"))
      (node (ref "SW29") (pin "1") (pinfunction "1_1") (pintype "unspecified"))
      (node (ref "SW38") (pin "1") (pinfunction "1_1") (pintype "unspecified"))
      (node (ref "SW45") (pin "1") (pinfunction "1_1") (pintype "unspecified"))
      (node (ref "SW54") (pin "1") (pinfunction "1_1") (pintype "unspecified"))
      (node (ref "SW6") (pin "1") (pinfunction "1_1") (pintype "unspecified"))
      (node (ref "SW61") (pin "1") (pinfunction "1_1") (pintype "unspecified"))
    )
    (net (code "10") (name "Key8") (class "Default")
      (node (ref "SW12") (pin "1") (pinfunction "1_1") (pintype "unspecified"))
      (node (ref "SW23") (pin "1") (pinfunction "1_1") (pintype "unspecified"))
      (node (ref "SW28") (pin "1") (pinfunction "1_1") (pintype "unspecified"))
      (node (ref "SW39") (pin "1") (pinfunction "1_1") (pintype "unspecified"))
      (node (ref "SW44") (pin "1") (pinfunction "1_1") (pintype "unspecified"))
      (node (ref "SW55") (pin "1") (pinfunction "1_1") (pintype "unspecified"))
      (node (ref "SW60") (pin "1") (pinfunction "1_1") (pintype "unspecified"))
      (node (ref "SW7") (pin "1") (pinfunction "1_1") (pintype "unspecified"))
    )
    (net (code "11") (name "KeyRead1") (class "Default")
      (node (ref "D1") (pin "1") (pinfunction "K_1") (pintype "unspecified"))
      (node (ref "D2") (pin "1") (pinfunction "K_1") (pintype "unspecified"))
      (node (ref "D3") (pin "1") (pinfunction "K_1") (pintype "unspecified"))
      (node (ref "D4") (pin "1") (pinfunction "K_1") (pintype "unspecified"))
      (node (ref "D5") (pin "1") (pinfunction "K_1") (pintype "unspecified"))
      (node (ref "D6") (pin "1") (pinfunction "K_1") (pintype "unspecified"))
      (node (ref "D7") (pin "1") (pinfunction "K_1") (pintype "unspecified"))
      (node (ref "D8") (pin "1") (pinfunction "K_1") (pintype "unspecified"))
    )
    (net (code "12") (name "KeyRead2") (class "Default")
      (node (ref "D10") (pin "1") (pinfunction "K_1") (pintype "unspecified"))
      (node (ref "D11") (pin "1") (pinfunction "K_1") (pintype "unspecified"))
      (node (ref "D12") (pin "1") (pinfunction "K_1") (pintype "unspecified"))
      (node (ref "D13") (pin "1") (pinfunction "K_1") (pintype "unspecified"))
      (node (ref "D14") (pin "1") (pinfunction "K_1") (pintype "unspecified"))
      (node (ref "D15") (pin "1") (pinfunction "K_1") (pintype "unspecified"))
      (node (ref "D16") (pin "1") (pinfunction "K_1") (pintype "unspecified"))
      (node (ref "D9") (pin "1") (pinfunction "K_1") (pintype "unspecified"))
    )
    (net (code "13") (name "KeyRead3") (class "Default")
      (node (ref "D25") (pin "1") (pinfunction "K_1") (pintype "unspecified"))
      (node (ref "D26") (pin "1") (pinfunction "K_1") (pintype "unspecified"))
      (node (ref "D27") (pin "1") (pinfunction "K_1") (pintype "unspecified"))
      (node (ref "D28") (pin "1") (pinfunction "K_1") (pintype "unspecified"))
      (node (ref "D29") (pin "1") (pinfunction "K_1") (pintype "unspecified"))
      (node (ref "D30") (pin "1") (pinfunction "K_1") (pintype "unspecified"))
      (node (ref "D31") (pin "1") (pinfunction "K_1") (pintype "unspecified"))
      (node (ref "D32") (pin "1") (pinfunction "K_1") (pintype "unspecified"))
    )
    (net (code "14") (name "KeyRead4") (class "Default")
      (node (ref "D17") (pin "1") (pinfunction "K_1") (pintype "unspecified"))
      (node (ref "D18") (pin "1") (pinfunction "K_1") (pintype "unspecified"))
      (node (ref "D19") (pin "1") (pinfunction "K_1") (pintype "unspecified"))
      (node (ref "D20") (pin "1") (pinfunction "K_1") (pintype "unspecified"))
      (node (ref "D21") (pin "1") (pinfunction "K_1") (pintype "unspecified"))
      (node (ref "D22") (pin "1") (pinfunction "K_1") (pintype "unspecified"))
      (node (ref "D23") (pin "1") (pinfunction "K_1") (pintype "unspecified"))
      (node (ref "D24") (pin "1") (pinfunction "K_1") (pintype "unspecified"))
    )
    (net (code "15") (name "KeyRead5") (class "Default")
      (node (ref "D57") (pin "1") (pinfunction "K_1") (pintype "unspecified"))
      (node (ref "D58") (pin "1") (pinfunction "K_1") (pintype "unspecified"))
      (node (ref "D59") (pin "1") (pinfunction "K_1") (pintype "unspecified"))
      (node (ref "D60") (pin "1") (pinfunction "K_1") (pintype "unspecified"))
      (node (ref "D61") (pin "1") (pinfunction "K_1") (pintype "unspecified"))
      (node (ref "D62") (pin "1") (pinfunction "K_1") (pintype "unspecified"))
      (node (ref "D63") (pin "1") (pinfunction "K_1") (pintype "unspecified"))
      (node (ref "D64") (pin "1") (pinfunction "K_1") (pintype "unspecified"))
    )
    (net (code "16") (name "KeyRead6") (class "Default")
      (node (ref "D49") (pin "1") (pinfunction "K_1") (pintype "unspecified"))
      (node (ref "D50") (pin "1") (pinfunction "K_1") (pintype "unspecified"))
      (node (ref "D51") (pin "1") (pinfunction "K_1") (pintype "unspecified"))
      (node (ref "D52") (pin "1") (pinfunction "K_1") (pintype "unspecified"))
      (node (ref "D53") (pin "1") (pinfunction "K_1") (pintype "unspecified"))
      (node (ref "D54") (pin "1") (pinfunction "K_1") (pintype "unspecified"))
      (node (ref "D55") (pin "1") (pinfunction "K_1") (pintype "unspecified"))
      (node (ref "D56") (pin "1") (pinfunction "K_1") (pintype "unspecified"))
    )
    (net (code "17") (name "KeyRead7") (class "Default")
      (node (ref "D33") (pin "1") (pinfunction "K_1") (pintype "unspecified"))
      (node (ref "D34") (pin "1") (pinfunction "K_1") (pintype "unspecified"))
      (node (ref "D35") (pin "1") (pinfunction "K_1") (pintype "unspecified"))
      (node (ref "D36") (pin "1") (pinfunction "K_1") (pintype "unspecified"))
      (node (ref "D37") (pin "1") (pinfunction "K_1") (pintype "unspecified"))
      (node (ref "D38") (pin "1") (pinfunction "K_1") (pintype "unspecified"))
      (node (ref "D39") (pin "1") (pinfunction "K_1") (pintype "unspecified"))
      (node (ref "D40") (pin "1") (pinfunction "K_1") (pintype "unspecified"))
    )
    (net (code "18") (name "KeyRead8") (class "Default")
      (node (ref "D41") (pin "1") (pinfunction "K_1") (pintype "unspecified"))
      (node (ref "D42") (pin "1") (pinfunction "K_1") (pintype "unspecified"))
      (node (ref "D43") (pin "1") (pinfunction "K_1") (pintype "unspecified"))
      (node (ref "D44") (pin "1") (pinfunction "K_1") (pintype "unspecified"))
      (node (ref "D45") (pin "1") (pinfunction "K_1") (pintype "unspecified"))
      (node (ref "D46") (pin "1") (pinfunction "K_1") (pintype "unspecified"))
      (node (ref "D47") (pin "1") (pinfunction "K_1") (pintype "unspecified"))
      (node (ref "D48") (pin "1") (pinfunction "K_1") (pintype "unspecified"))
    )
    (net (code "19") (name "LEDdata") (class "Default")
      (node (ref "LED49") (pin "4") (pinfunction "DIN_4") (pintype "unspecified"))
    )
    (net (code "20") (name "LEDext") (class "Default")
      (node (ref "LED11") (pin "2") (pinfunction "DOUT_2") (pintype "unspecified"))
    )
    (net (code "21") (name "Net-(D1-A)") (class "Default")
      (node (ref "D1") (pin "2") (pinfunction "A_2") (pintype "unspecified"))
      (node (ref "SW2") (pin "2") (pinfunction "2_2") (pintype "unspecified"))
    )
    (net (code "22") (name "Net-(D2-A)") (class "Default")
      (node (ref "D2") (pin "2") (pinfunction "A_2") (pintype "unspecified"))
      (node (ref "SW3") (pin "2") (pinfunction "2_2") (pintype "unspecified"))
    )
    (net (code "23") (name "Net-(D3-A)") (class "Default")
      (node (ref "D3") (pin "2") (pinfunction "A_2") (pintype "unspecified"))
      (node (ref "SW4") (pin "2") (pinfunction "2_2") (pintype "unspecified"))
    )
    (net (code "24") (name "Net-(D4-A)") (class "Default")
      (node (ref "D4") (pin "2") (pinfunction "A_2") (pintype "unspecified"))
      (node (ref "SW5") (pin "2") (pinfunction "2_2") (pintype "unspecified"))
    )
    (net (code "25") (name "Net-(D5-A)") (class "Default")
      (node (ref "D5") (pin "2") (pinfunction "A_2") (pintype "unspecified"))
      (node (ref "SW6") (pin "2") (pinfunction "2_2") (pintype "unspecified"))
    )
    (net (code "26") (name "Net-(D6-A)") (class "Default")
      (node (ref "D6") (pin "2") (pinfunction "A_2") (pintype "unspecified"))
      (node (ref "SW7") (pin "2") (pinfunction "2_2") (pintype "unspecified"))
    )
    (net (code "27") (name "Net-(D7-A)") (class "Default")
      (node (ref "D7") (pin "2") (pinfunction "A_2") (pintype "unspecified"))
      (node (ref "SW8") (pin "2") (pinfunction "2_2") (pintype "unspecified"))
    )
    (net (code "28") (name "Net-(D8-A)") (class "Default")
      (node (ref "D8") (pin "2") (pinfunction "A_2") (pintype "unspecified"))
      (node (ref "SW9") (pin "2") (pinfunction "2_2") (pintype "unspecified"))
    )
    (net (code "29") (name "Net-(D9-A)") (class "Default")
      (node (ref "D9") (pin "2") (pinfunction "A_2") (pintype "unspecified"))
      (node (ref "SW10") (pin "2") (pinfunction "2_2") (pintype "unspecified"))
    )
    (net (code "30") (name "Net-(D10-A)") (class "Default")
      (node (ref "D10") (pin "2") (pinfunction "A_2") (pintype "unspecified"))
      (node (ref "SW11") (pin "2") (pinfunction "2_2") (pintype "unspecified"))
    )
    (net (code "31") (name "Net-(D11-A)") (class "Default")
      (node (ref "D11") (pin "2") (pinfunction "A_2") (pintype "unspecified"))
      (node (ref "SW13") (pin "2") (pinfunction "2_2") (pintype "unspecified"))
    )
    (net (code "32") (name "Net-(D12-A)") (class "Default")
      (node (ref "D12") (pin "2") (pinfunction "A_2") (pintype "unspecified"))
      (node (ref "SW14") (pin "2") (pinfunction "2_2") (pintype "unspecified"))
    )
    (net (code "33") (name "Net-(D13-A)") (class "Default")
      (node (ref "D13") (pin "2") (pinfunction "A_2") (pintype "unspecified"))
      (node (ref "SW15") (pin "2") (pinfunction "2_2") (pintype "unspecified"))
    )
    (net (code "34") (name "Net-(D14-A)") (class "Default")
      (node (ref "D14") (pin "2") (pinfunction "A_2") (pintype "unspecified"))
      (node (ref "SW16") (pin "2") (pinfunction "2_2") (pintype "unspecified"))
    )
    (net (code "35") (name "Net-(D15-A)") (class "Default")
      (node (ref "D15") (pin "2") (pinfunction "A_2") (pintype "unspecified"))
      (node (ref "SW17") (pin "2") (pinfunction "2_2") (pintype "unspecified"))
    )
    (net (code "36") (name "Net-(D16-A)") (class "Default")
      (node (ref "D16") (pin "2") (pinfunction "A_2") (pintype "unspecified"))
      (node (ref "SW12") (pin "2") (pinfunction "2_2") (pintype "unspecified"))
    )
    (net (code "37") (name "Net-(D17-A)") (class "Default")
      (node (ref "D17") (pin "2") (pinfunction "A_2") (pintype "unspecified"))
      (node (ref "SW23") (pin "2") (pinfunction "2_2") (pintype "unspecified"))
    )
    (net (code "38") (name "Net-(D18-A)") (class "Default")
      (node (ref "D18") (pin "2") (pinfunction "A_2") (pintype "unspecified"))
      (node (ref "SW18") (pin "2") (pinfunction "2_2") (pintype "unspecified"))
    )
    (net (code "39") (name "Net-(D19-A)") (class "Default")
      (node (ref "D19") (pin "2") (pinfunction "A_2") (pintype "unspecified"))
      (node (ref "SW19") (pin "2") (pinfunction "2_2") (pintype "unspecified"))
    )
    (net (code "40") (name "Net-(D20-A)") (class "Default")
      (node (ref "D20") (pin "2") (pinfunction "A_2") (pintype "unspecified"))
      (node (ref "SW20") (pin "2") (pinfunction "2_2") (pintype "unspecified"))
    )
    (net (code "41") (name "Net-(D21-A)") (class "Default")
      (node (ref "D21") (pin "2") (pinfunction "A_2") (pintype "unspecified"))
      (node (ref "SW21") (pin "2") (pinfunction "2_2") (pintype "unspecified"))
    )
    (net (code "42") (name "Net-(D22-A)") (class "Default")
      (node (ref "D22") (pin "2") (pinfunction "A_2") (pintype "unspecified"))
      (node (ref "SW22") (pin "2") (pinfunction "2_2") (pintype "unspecified"))
    )
    (net (code "43") (name "Net-(D23-A)") (class "Default")
      (node (ref "D23") (pin "2") (pinfunction "A_2") (pintype "unspecified"))
      (node (ref "SW24") (pin "2") (pinfunction "2_2") (pintype "unspecified"))
    )
    (net (code "44") (name "Net-(D24-A)") (class "Default")
      (node (ref "D24") (pin "2") (pinfunction "A_2") (pintype "unspecified"))
      (node (ref "SW25") (pin "2") (pinfunction "2_2") (pintype "unspecified"))
    )
    (net (code "45") (name "Net-(D25-A)") (class "Default")
      (node (ref "D25") (pin "2") (pinfunction "A_2") (pintype "unspecified"))
      (node (ref "SW26") (pin "2") (pinfunction "2_2") (pintype "unspecified"))
    )
    (net (code "46") (name "Net-(D26-A)") (class "Default")
      (node (ref "D26") (pin "2") (pinfunction "A_2") (pintype "unspecified"))
      (node (ref "SW27") (pin "2") (pinfunction "2_2") (pintype "unspecified"))
    )
    (net (code "47") (name "Net-(D27-A)") (class "Default")
      (node (ref "D27") (pin "2") (pinfunction "A_2") (pintype "unspecified"))
      (node (ref "SW28") (pin "2") (pinfunction "2_2") (pintype "unspecified"))
    )
    (net (code "48") (name "Net-(D28-A)") (class "Default")
      (node (ref "D28") (pin "2") (pinfunction "A_2") (pintype "unspecified"))
      (node (ref "SW29") (pin "2") (pinfunction "2_2") (pintype "unspecified"))
    )
    (net (code "49") (name "Net-(D29-A)") (class "Default")
      (node (ref "D29") (pin "2") (pinfunction "A_2") (pintype "unspecified"))
      (node (ref "SW30") (pin "2") (pinfunction "2_2") (pintype "unspecified"))
    )
    (net (code "50") (name "Net-(D30-A)") (class "Default")
      (node (ref "D30") (pin "2") (pinfunction "A_2") (pintype "unspecified"))
      (node (ref "SW31") (pin "2") (pinfunction "2_2") (pintype "unspecified"))
    )
    (net (code "51") (name "Net-(D31-A)") (class "Default")
      (node (ref "D31") (pin "2") (pinfunction "A_2") (pintype "unspecified"))
      (node (ref "SW32") (pin "2") (pinfunction "2_2") (pintype "unspecified"))
    )
    (net (code "52") (name "Net-(D32-A)") (class "Default")
      (node (ref "D32") (pin "2") (pinfunction "A_2") (pintype "unspecified"))
      (node (ref "SW33") (pin "2") (pinfunction "2_2") (pintype "unspecified"))
    )
    (net (code "53") (name "Net-(D33-A)") (class "Default")
      (node (ref "D33") (pin "2") (pinfunction "A_2") (pintype "unspecified"))
      (node (ref "SW34") (pin "2") (pinfunction "2_2") (pintype "unspecified"))
    )
    (net (code "54") (name "Net-(D34-A)") (class "Default")
      (node (ref "D34") (pin "2") (pinfunction "A_2") (pintype "unspecified"))
      (node (ref "SW35") (pin "2") (pinfunction "2_2") (pintype "unspecified"))
    )
    (net (code "55") (name "Net-(D35-A)") (class "Default")
      (node (ref "D35") (pin "2") (pinfunction "A_2") (pintype "unspecified"))
      (node (ref "SW36") (pin "2") (pinfunction "2_2") (pintype "unspecified"))
    )
    (net (code "56") (name "Net-(D36-A)") (class "Default")
      (node (ref "D36") (pin "2") (pinfunction "A_2") (pintype "unspecified"))
      (node (ref "SW37") (pin "2") (pinfunction "2_2") (pintype "unspecified"))
    )
    (net (code "57") (name "Net-(D37-A)") (class "Default")
      (node (ref "D37") (pin "2") (pinfunction "A_2") (pintype "unspecified"))
      (node (ref "SW38") (pin "2") (pinfunction "2_2") (pintype "unspecified"))
    )
    (net (code "58") (name "Net-(D38-A)") (class "Default")
      (node (ref "D38") (pin "2") (pinfunction "A_2") (pintype "unspecified"))
      (node (ref "SW39") (pin "2") (pinfunction "2_2") (pintype "unspecified"))
    )
    (net (code "59") (name "Net-(D39-A)") (class "Default")
      (node (ref "D39") (pin "2") (pinfunction "A_2") (pintype "unspecified"))
      (node (ref "SW40") (pin "2") (pinfunction "2_2") (pintype "unspecified"))
    )
    (net (code "60") (name "Net-(D40-A)") (class "Default")
      (node (ref "D40") (pin "2") (pinfunction "A_2") (pintype "unspecified"))
      (node (ref "SW41") (pin "2") (pinfunction "2_2") (pintype "unspecified"))
    )
    (net (code "61") (name "Net-(D41-A)") (class "Default")
      (node (ref "D41") (pin "2") (pinfunction "A_2") (pintype "unspecified"))
      (node (ref "SW42") (pin "2") (pinfunction "2_2") (pintype "unspecified"))
    )
    (net (code "62") (name "Net-(D42-A)") (class "Default")
      (node (ref "D42") (pin "2") (pinfunction "A_2") (pintype "unspecified"))
      (node (ref "SW43") (pin "2") (pinfunction "2_2") (pintype "unspecified"))
    )
    (net (code "63") (name "Net-(D43-A)") (class "Default")
      (node (ref "D43") (pin "2") (pinfunction "A_2") (pintype "unspecified"))
      (node (ref "SW45") (pin "2") (pinfunction "2_2") (pintype "unspecified"))
    )
    (net (code "64") (name "Net-(D44-A)") (class "Default")
      (node (ref "D44") (pin "2") (pinfunction "A_2") (pintype "unspecified"))
      (node (ref "SW46") (pin "2") (pinfunction "2_2") (pintype "unspecified"))
    )
    (net (code "65") (name "Net-(D45-A)") (class "Default")
      (node (ref "D45") (pin "2") (pinfunction "A_2") (pintype "unspecified"))
      (node (ref "SW47") (pin "2") (pinfunction "2_2") (pintype "unspecified"))
    )
    (net (code "66") (name "Net-(D46-A)") (class "Default")
      (node (ref "D46") (pin "2") (pinfunction "A_2") (pintype "unspecified"))
      (node (ref "SW48") (pin "2") (pinfunction "2_2") (pintype "unspecified"))
    )
    (net (code "67") (name "Net-(D47-A)") (class "Default")
      (node (ref "D47") (pin "2") (pinfunction "A_2") (pintype "unspecified"))
      (node (ref "SW49") (pin "2") (pinfunction "2_2") (pintype "unspecified"))
    )
    (net (code "68") (name "Net-(D48-A)") (class "Default")
      (node (ref "D48") (pin "2") (pinfunction "A_2") (pintype "unspecified"))
      (node (ref "SW44") (pin "2") (pinfunction "2_2") (pintype "unspecified"))
    )
    (net (code "69") (name "Net-(D49-A)") (class "Default")
      (node (ref "D49") (pin "2") (pinfunction "A_2") (pintype "unspecified"))
      (node (ref "SW55") (pin "2") (pinfunction "2_2") (pintype "unspecified"))
    )
    (net (code "70") (name "Net-(D50-A)") (class "Default")
      (node (ref "D50") (pin "2") (pinfunction "A_2") (pintype "unspecified"))
      (node (ref "SW50") (pin "2") (pinfunction "2_2") (pintype "unspecified"))
    )
    (net (code "71") (name "Net-(D51-A)") (class "Default")
      (node (ref "D51") (pin "2") (pinfunction "A_2") (pintype "unspecified"))
      (node (ref "SW51") (pin "2") (pinfunction "2_2") (pintype "unspecified"))
    )
    (net (code "72") (name "Net-(D52-A)") (class "Default")
      (node (ref "D52") (pin "2") (pinfunction "A_2") (pintype "unspecified"))
      (node (ref "SW52") (pin "2") (pinfunction "2_2") (pintype "unspecified"))
    )
    (net (code "73") (name "Net-(D53-A)") (class "Default")
      (node (ref "D53") (pin "2") (pinfunction "A_2") (pintype "unspecified"))
      (node (ref "SW53") (pin "2") (pinfunction "2_2") (pintype "unspecified"))
    )
    (net (code "74") (name "Net-(D54-A)") (class "Default")
      (node (ref "D54") (pin "2") (pinfunction "A_2") (pintype "unspecified"))
      (node (ref "SW54") (pin "2") (pinfunction "2_2") (pintype "unspecified"))
    )
    (net (code "75") (name "Net-(D55-A)") (class "Default")
      (node (ref "D55") (pin "2") (pinfunction "A_2") (pintype "unspecified"))
      (node (ref "SW56") (pin "2") (pinfunction "2_2") (pintype "unspecified"))
    )
    (net (code "76") (name "Net-(D56-A)") (class "Default")
      (node (ref "D56") (pin "2") (pinfunction "A_2") (pintype "unspecified"))
      (node (ref "SW57") (pin "2") (pinfunction "2_2") (pintype "unspecified"))
    )
    (net (code "77") (name "Net-(D57-A)") (class "Default")
      (node (ref "D57") (pin "2") (pinfunction "A_2") (pintype "unspecified"))
      (node (ref "SW58") (pin "2") (pinfunction "2_2") (pintype "unspecified"))
    )
    (net (code "78") (name "Net-(D58-A)") (class "Default")
      (node (ref "D58") (pin "2") (pinfunction "A_2") (pintype "unspecified"))
      (node (ref "SW59") (pin "2") (pinfunction "2_2") (pintype "unspecified"))
    )
    (net (code "79") (name "Net-(D59-A)") (class "Default")
      (node (ref "D59") (pin "2") (pinfunction "A_2") (pintype "unspecified"))
      (node (ref "SW60") (pin "2") (pinfunction "2_2") (pintype "unspecified"))
    )
    (net (code "80") (name "Net-(D60-A)") (class "Default")
      (node (ref "D60") (pin "2") (pinfunction "A_2") (pintype "unspecified"))
      (node (ref "SW61") (pin "2") (pinfunction "2_2") (pintype "unspecified"))
    )
    (net (code "81") (name "Net-(D61-A)") (class "Default")
      (node (ref "D61") (pin "2") (pinfunction "A_2") (pintype "unspecified"))
      (node (ref "SW62") (pin "2") (pinfunction "2_2") (pintype "unspecified"))
    )
    (net (code "82") (name "Net-(D62-A)") (class "Default")
      (node (ref "D62") (pin "2") (pinfunction "A_2") (pintype "unspecified"))
      (node (ref "SW63") (pin "2") (pinfunction "2_2") (pintype "unspecified"))
    )
    (net (code "83") (name "Net-(D63-A)") (class "Default")
      (node (ref "D63") (pin "2") (pinfunction "A_2") (pintype "unspecified"))
      (node (ref "SW64") (pin "2") (pinfunction "2_2") (pintype "unspecified"))
    )
    (net (code "84") (name "Net-(D64-A)") (class "Default")
      (node (ref "D64") (pin "2") (pinfunction "A_2") (pintype "unspecified"))
      (node (ref "SW65") (pin "2") (pinfunction "2_2") (pintype "unspecified"))
    )
    (net (code "85") (name "Net-(LED1-DIN)") (class "Default")
      (node (ref "LED1") (pin "4") (pinfunction "DIN_4") (pintype "unspecified"))
      (node (ref "LED22") (pin "2") (pinfunction "DOUT_2") (pintype "unspecified"))
    )
    (net (code "86") (name "Net-(LED1-DOUT)") (class "Default")
      (node (ref "LED1") (pin "2") (pinfunction "DOUT_2") (pintype "unspecified"))
      (node (ref "LED2") (pin "4") (pinfunction "DIN_4") (pintype "unspecified"))
    )
    (net (code "87") (name "Net-(LED2-DOUT)") (class "Default")
      (node (ref "LED2") (pin "2") (pinfunction "DOUT_2") (pintype "unspecified"))
      (node (ref "LED4") (pin "4") (pinfunction "DIN_4") (pintype "unspecified"))
    )
    (net (code "88") (name "Net-(LED3-DIN)") (class "Default")
      (node (ref "LED3") (pin "4") (pinfunction "DIN_4") (pintype "unspecified"))
      (node (ref "LED4") (pin "2") (pinfunction "DOUT_2") (pintype "unspecified"))
    )
    (net (code "89") (name "Net-(LED3-DOUT)") (class "Default")
      (node (ref "LED3") (pin "2") (pinfunction "DOUT_2") (pintype "unspecified"))
      (node (ref "LED8") (pin "4") (pinfunction "DIN_4") (pintype "unspecified"))
    )
    (net (code "90") (name "Net-(LED5-DIN)") (class "Default")
      (node (ref "LED5") (pin "4") (pinfunction "DIN_4") (pintype "unspecified"))
      (node (ref "LED7") (pin "2") (pinfunction "DOUT_2") (pintype "unspecified"))
    )
    (net (code "91") (name "Net-(LED5-DOUT)") (class "Default")
      (node (ref "LED5") (pin "2") (pinfunction "DOUT_2") (pintype "unspecified"))
      (node (ref "LED6") (pin "4") (pinfunction "DIN_4") (pintype "unspecified"))
    )
    (net (code "92") (name "Net-(LED7-DIN)") (class "Default")
      (node (ref "LED7") (pin "4") (pinfunction "DIN_4") (pintype "unspecified"))
      (node (ref "LED8") (pin "2") (pinfunction "DOUT_2") (pintype "unspecified"))
    )
    (net (code "93") (name "Net-(LED10-DIN)") (class "Default")
      (node (ref "LED10") (pin "4") (pinfunction "DIN_4") (pintype "unspecified"))
      (node (ref "LED9") (pin "2") (pinfunction "DOUT_2") (pintype "unspecified"))
    )
    (net (code "94") (name "Net-(LED10-DOUT)") (class "Default")
      (node (ref "LED10") (pin "2") (pinfunction "DOUT_2") (pintype "unspecified"))
      (node (ref "LED12") (pin "4") (pinfunction "DIN_4") (pintype "unspecified"))
    )
    (net (code "95") (name "Net-(LED11-DIN)") (class "Default")
      (node (ref "LED11") (pin "4") (pinfunction "DIN_4") (pintype "unspecified"))
      (node (ref "LED12") (pin "2") (pinfunction "DOUT_2") (pintype "unspecified"))
    )
    (net (code "96") (name "Net-(LED13-DIN)") (class "Default")
      (node (ref "LED13") (pin "4") (pinfunction "DIN_4") (pintype "unspecified"))
      (node (ref "LED15") (pin "2") (pinfunction "DOUT_2") (pintype "unspecified"))
    )
    (net (code "97") (name "Net-(LED13-DOUT)") (class "Default")
      (node (ref "LED13") (pin "2") (pinfunction "DOUT_2") (pintype "unspecified"))
      (node (ref "LED14") (pin "4") (pinfunction "DIN_4") (pintype "unspecified"))
    )
    (net (code "98") (name "Net-(LED14-DOUT)") (class "Default")
      (node (ref "LED14") (pin "2") (pinfunction "DOUT_2") (pintype "unspecified"))
      (node (ref "LED9") (pin "4") (pinfunction "DIN_4") (pintype "unspecified"))
    )
    (net (code "99") (name "Net-(LED15-DIN)") (class "Default")
      (node (ref "LED15") (pin "4") (pinfunction "DIN_4") (pintype "unspecified"))
      (node (ref "LED16") (pin "2") (pinfunction "DOUT_2") (pintype "unspecified"))
    )
    (net (code "100") (name "Net-(LED16-DIN)") (class "Default")
      (node (ref "LED16") (pin "4") (pinfunction "DIN_4") (pintype "unspecified"))
      (node (ref "LED6") (pin "2") (pinfunction "DOUT_2") (pintype "unspecified"))
    )
    (net (code "101") (name "Net-(LED17-DIN)") (class "Default")
      (node (ref "LED17") (pin "4") (pinfunction "DIN_4") (pintype "unspecified"))
      (node (ref "LED27") (pin "2") (pinfunction "DOUT_2") (pintype "unspecified"))
    )
    (net (code "102") (name "Net-(LED17-DOUT)") (class "Default")
      (node (ref "LED17") (pin "2") (pinfunction "DOUT_2") (pintype "unspecified"))
      (node (ref "LED18") (pin "4") (pinfunction "DIN_4") (pintype "unspecified"))
    )
    (net (code "103") (name "Net-(LED18-DOUT)") (class "Default")
      (node (ref "LED18") (pin "2") (pinfunction "DOUT_2") (pintype "unspecified"))
      (node (ref "LED20") (pin "4") (pinfunction "DIN_4") (pintype "unspecified"))
    )
    (net (code "104") (name "Net-(LED19-DIN)") (class "Default")
      (node (ref "LED19") (pin "4") (pinfunction "DIN_4") (pintype "unspecified"))
      (node (ref "LED20") (pin "2") (pinfunction "DOUT_2") (pintype "unspecified"))
    )
    (net (code "105") (name "Net-(LED19-DOUT)") (class "Default")
      (node (ref "LED19") (pin "2") (pinfunction "DOUT_2") (pintype "unspecified"))
      (node (ref "LED24") (pin "4") (pinfunction "DIN_4") (pintype "unspecified"))
    )
    (net (code "106") (name "Net-(LED21-DIN)") (class "Default")
      (node (ref "LED21") (pin "4") (pinfunction "DIN_4") (pintype "unspecified"))
      (node (ref "LED23") (pin "2") (pinfunction "DOUT_2") (pintype "unspecified"))
    )
    (net (code "107") (name "Net-(LED21-DOUT)") (class "Default")
      (node (ref "LED21") (pin "2") (pinfunction "DOUT_2") (pintype "unspecified"))
      (node (ref "LED22") (pin "4") (pinfunction "DIN_4") (pintype "unspecified"))
    )
    (net (code "108") (name "Net-(LED23-DIN)") (class "Default")
      (node (ref "LED23") (pin "4") (pinfunction "DIN_4") (pintype "unspecified"))
      (node (ref "LED24") (pin "2") (pinfunction "DOUT_2") (pintype "unspecified"))
    )
    (net (code "109") (name "Net-(LED25-DIN)") (class "Default")
      (node (ref "LED25") (pin "4") (pinfunction "DIN_4") (pintype "unspecified"))
      (node (ref "LED30") (pin "2") (pinfunction "DOUT_2") (pintype "unspecified"))
    )
    (net (code "110") (name "Net-(LED25-DOUT)") (class "Default")
      (node (ref "LED25") (pin "2") (pinfunction "DOUT_2") (pintype "unspecified"))
      (node (ref "LED26") (pin "4") (pinfunction "DIN_4") (pintype "unspecified"))
    )
    (net (code "111") (name "Net-(LED26-DOUT)") (class "Default")
      (node (ref "LED26") (pin "2") (pinfunction "DOUT_2") (pintype "unspecified"))
      (node (ref "LED28") (pin "4") (pinfunction "DIN_4") (pintype "unspecified"))
    )
    (net (code "112") (name "Net-(LED27-DIN)") (class "Default")
      (node (ref "LED27") (pin "4") (pinfunction "DIN_4") (pintype "unspecified"))
      (node (ref "LED28") (pin "2") (pinfunction "DOUT_2") (pintype "unspecified"))
    )
    (net (code "113") (name "Net-(LED29-DIN)") (class "Default")
      (node (ref "LED29") (pin "4") (pinfunction "DIN_4") (pintype "unspecified"))
      (node (ref "LED31") (pin "2") (pinfunction "DOUT_2") (pintype "unspecified"))
    )
    (net (code "114") (name "Net-(LED29-DOUT)") (class "Default")
      (node (ref "LED29") (pin "2") (pinfunction "DOUT_2") (pintype "unspecified"))
      (node (ref "LED30") (pin "4") (pinfunction "DIN_4") (pintype "unspecified"))
    )
    (net (code "115") (name "Net-(LED31-DIN)") (class "Default")
      (node (ref "LED31") (pin "4") (pinfunction "DIN_4") (pintype "unspecified"))
      (node (ref "LED32") (pin "2") (pinfunction "DOUT_2") (pintype "unspecified"))
    )
    (net (code "116") (name "Net-(LED32-DIN)") (class "Default")
      (node (ref "LED32") (pin "4") (pinfunction "DIN_4") (pintype "unspecified"))
      (node (ref "LED43") (pin "2") (pinfunction "DOUT_2") (pintype "unspecified"))
    )
    (net (code "117") (name "Net-(LED33-DIN)") (class "Default")
      (node (ref "LED33") (pin "4") (pinfunction "DIN_4") (pintype "unspecified"))
      (node (ref "LED59") (pin "2") (pinfunction "DOUT_2") (pintype "unspecified"))
    )
    (net (code "118") (name "Net-(LED33-DOUT)") (class "Default")
      (node (ref "LED33") (pin "2") (pinfunction "DOUT_2") (pintype "unspecified"))
      (node (ref "LED34") (pin "4") (pinfunction "DIN_4") (pintype "unspecified"))
    )
    (net (code "119") (name "Net-(LED34-DOUT)") (class "Default")
      (node (ref "LED34") (pin "2") (pinfunction "DOUT_2") (pintype "unspecified"))
      (node (ref "LED36") (pin "4") (pinfunction "DIN_4") (pintype "unspecified"))
    )
    (net (code "120") (name "Net-(LED35-DIN)") (class "Default")
      (node (ref "LED35") (pin "4") (pinfunction "DIN_4") (pintype "unspecified"))
      (node (ref "LED36") (pin "2") (pinfunction "DOUT_2") (pintype "unspecified"))
    )
    (net (code "121") (name "Net-(LED35-DOUT)") (class "Default")
      (node (ref "LED35") (pin "2") (pinfunction "DOUT_2") (pintype "unspecified"))
      (node (ref "LED40") (pin "4") (pinfunction "DIN_4") (pintype "unspecified"))
    )
    (net (code "122") (name "Net-(LED37-DIN)") (class "Default")
      (node (ref "LED37") (pin "4") (pinfunction "DIN_4") (pintype "unspecified"))
      (node (ref "LED39") (pin "2") (pinfunction "DOUT_2") (pintype "unspecified"))
    )
    (net (code "123") (name "Net-(LED37-DOUT)") (class "Default")
      (node (ref "LED37") (pin "2") (pinfunction "DOUT_2") (pintype "unspecified"))
      (node (ref "LED38") (pin "4") (pinfunction "DIN_4") (pintype "unspecified"))
    )
    (net (code "124") (name "Net-(LED38-DOUT)") (class "Default")
      (node (ref "LED38") (pin "2") (pinfunction "DOUT_2") (pintype "unspecified"))
      (node (ref "LED48") (pin "4") (pinfunction "DIN_4") (pintype "unspecified"))
    )
    (net (code "125") (name "Net-(LED39-DIN)") (class "Default")
      (node (ref "LED39") (pin "4") (pinfunction "DIN_4") (pintype "unspecified"))
      (node (ref "LED40") (pin "2") (pinfunction "DOUT_2") (pintype "unspecified"))
    )
    (net (code "126") (name "Net-(LED41-DIN)") (class "Default")
      (node (ref "LED41") (pin "4") (pinfunction "DIN_4") (pintype "unspecified"))
      (node (ref "LED46") (pin "2") (pinfunction "DOUT_2") (pintype "unspecified"))
    )
    (net (code "127") (name "Net-(LED41-DOUT)") (class "Default")
      (node (ref "LED41") (pin "2") (pinfunction "DOUT_2") (pintype "unspecified"))
      (node (ref "LED42") (pin "4") (pinfunction "DIN_4") (pintype "unspecified"))
    )
    (net (code "128") (name "Net-(LED42-DOUT)") (class "Default")
      (node (ref "LED42") (pin "2") (pinfunction "DOUT_2") (pintype "unspecified"))
      (node (ref "LED44") (pin "4") (pinfunction "DIN_4") (pintype "unspecified"))
    )
    (net (code "129") (name "Net-(LED43-DIN)") (class "Default")
      (node (ref "LED43") (pin "4") (pinfunction "DIN_4") (pintype "unspecified"))
      (node (ref "LED44") (pin "2") (pinfunction "DOUT_2") (pintype "unspecified"))
    )
    (net (code "130") (name "Net-(LED45-DIN)") (class "Default")
      (node (ref "LED45") (pin "4") (pinfunction "DIN_4") (pintype "unspecified"))
      (node (ref "LED47") (pin "2") (pinfunction "DOUT_2") (pintype "unspecified"))
    )
    (net (code "131") (name "Net-(LED45-DOUT)") (class "Default")
      (node (ref "LED45") (pin "2") (pinfunction "DOUT_2") (pintype "unspecified"))
      (node (ref "LED46") (pin "4") (pinfunction "DIN_4") (pintype "unspecified"))
    )
    (net (code "132") (name "Net-(LED47-DIN)") (class "Default")
      (node (ref "LED47") (pin "4") (pinfunction "DIN_4") (pintype "unspecified"))
      (node (ref "LED48") (pin "2") (pinfunction "DOUT_2") (pintype "unspecified"))
    )
    (net (code "133") (name "Net-(LED49-DOUT)") (class "Default")
      (node (ref "LED49") (pin "2") (pinfunction "DOUT_2") (pintype "unspecified"))
      (node (ref "LED50") (pin "4") (pinfunction "DIN_4") (pintype "unspecified"))
    )
    (net (code "134") (name "Net-(LED50-DOUT)") (class "Default")
      (node (ref "LED50") (pin "2") (pinfunction "DOUT_2") (pintype "unspecified"))
      (node (ref "LED52") (pin "4") (pinfunction "DIN_4") (pintype "unspecified"))
    )
    (net (code "135") (name "Net-(LED51-DIN)") (class "Default")
      (node (ref "LED51") (pin "4") (pinfunction "DIN_4") (pintype "unspecified"))
      (node (ref "LED52") (pin "2") (pinfunction "DOUT_2") (pintype "unspecified"))
    )
    (net (code "136") (name "Net-(LED51-DOUT)") (class "Default")
      (node (ref "LED51") (pin "2") (pinfunction "DOUT_2") (pintype "unspecified"))
      (node (ref "LED56") (pin "4") (pinfunction "DIN_4") (pintype "unspecified"))
    )
    (net (code "137") (name "Net-(LED53-DIN)") (class "Default")
      (node (ref "LED53") (pin "4") (pinfunction "DIN_4") (pintype "unspecified"))
      (node (ref "LED55") (pin "2") (pinfunction "DOUT_2") (pintype "unspecified"))
    )
    (net (code "138") (name "Net-(LED53-DOUT)") (class "Default")
      (node (ref "LED53") (pin "2") (pinfunction "DOUT_2") (pintype "unspecified"))
      (node (ref "LED54") (pin "4") (pinfunction "DIN_4") (pintype "unspecified"))
    )
    (net (code "139") (name "Net-(LED54-DOUT)") (class "Default")
      (node (ref "LED54") (pin "2") (pinfunction "DOUT_2") (pintype "unspecified"))
      (node (ref "LED64") (pin "4") (pinfunction "DIN_4") (pintype "unspecified"))
    )
    (net (code "140") (name "Net-(LED55-DIN)") (class "Default")
      (node (ref "LED55") (pin "4") (pinfunction "DIN_4") (pintype "unspecified"))
      (node (ref "LED56") (pin "2") (pinfunction "DOUT_2") (pintype "unspecified"))
    )
    (net (code "141") (name "Net-(LED57-DIN)") (class "Default")
      (node (ref "LED57") (pin "4") (pinfunction "DIN_4") (pintype "unspecified"))
      (node (ref "LED62") (pin "2") (pinfunction "DOUT_2") (pintype "unspecified"))
    )
    (net (code "142") (name "Net-(LED57-DOUT)") (class "Default")
      (node (ref "LED57") (pin "2") (pinfunction "DOUT_2") (pintype "unspecified"))
      (node (ref "LED58") (pin "4") (pinfunction "DIN_4") (pintype "unspecified"))
    )
    (net (code "143") (name "Net-(LED58-DOUT)") (class "Default")
      (node (ref "LED58") (pin "2") (pinfunction "DOUT_2") (pintype "unspecified"))
      (node (ref "LED60") (pin "4") (pinfunction "DIN_4") (pintype "unspecified"))
    )
    (net (code "144") (name "Net-(LED59-DIN)") (class "Default")
      (node (ref "LED59") (pin "4") (pinfunction "DIN_4") (pintype "unspecified"))
      (node (ref "LED60") (pin "2") (pinfunction "DOUT_2") (pintype "unspecified"))
    )
    (net (code "145") (name "Net-(LED61-DIN)") (class "Default")
      (node (ref "LED61") (pin "4") (pinfunction "DIN_4") (pintype "unspecified"))
      (node (ref "LED63") (pin "2") (pinfunction "DOUT_2") (pintype "unspecified"))
    )
    (net (code "146") (name "Net-(LED61-DOUT)") (class "Default")
      (node (ref "LED61") (pin "2") (pinfunction "DOUT_2") (pintype "unspecified"))
      (node (ref "LED62") (pin "4") (pinfunction "DIN_4") (pintype "unspecified"))
    )
    (net (code "147") (name "Net-(LED63-DIN)") (class "Default")
      (node (ref "LED63") (pin "4") (pinfunction "DIN_4") (pintype "unspecified"))
      (node (ref "LED64") (pin "2") (pinfunction "DOUT_2") (pintype "unspecified"))
    )
  )
)
